# All.net
KiCad netlist of a schematic drawn in EAGLE
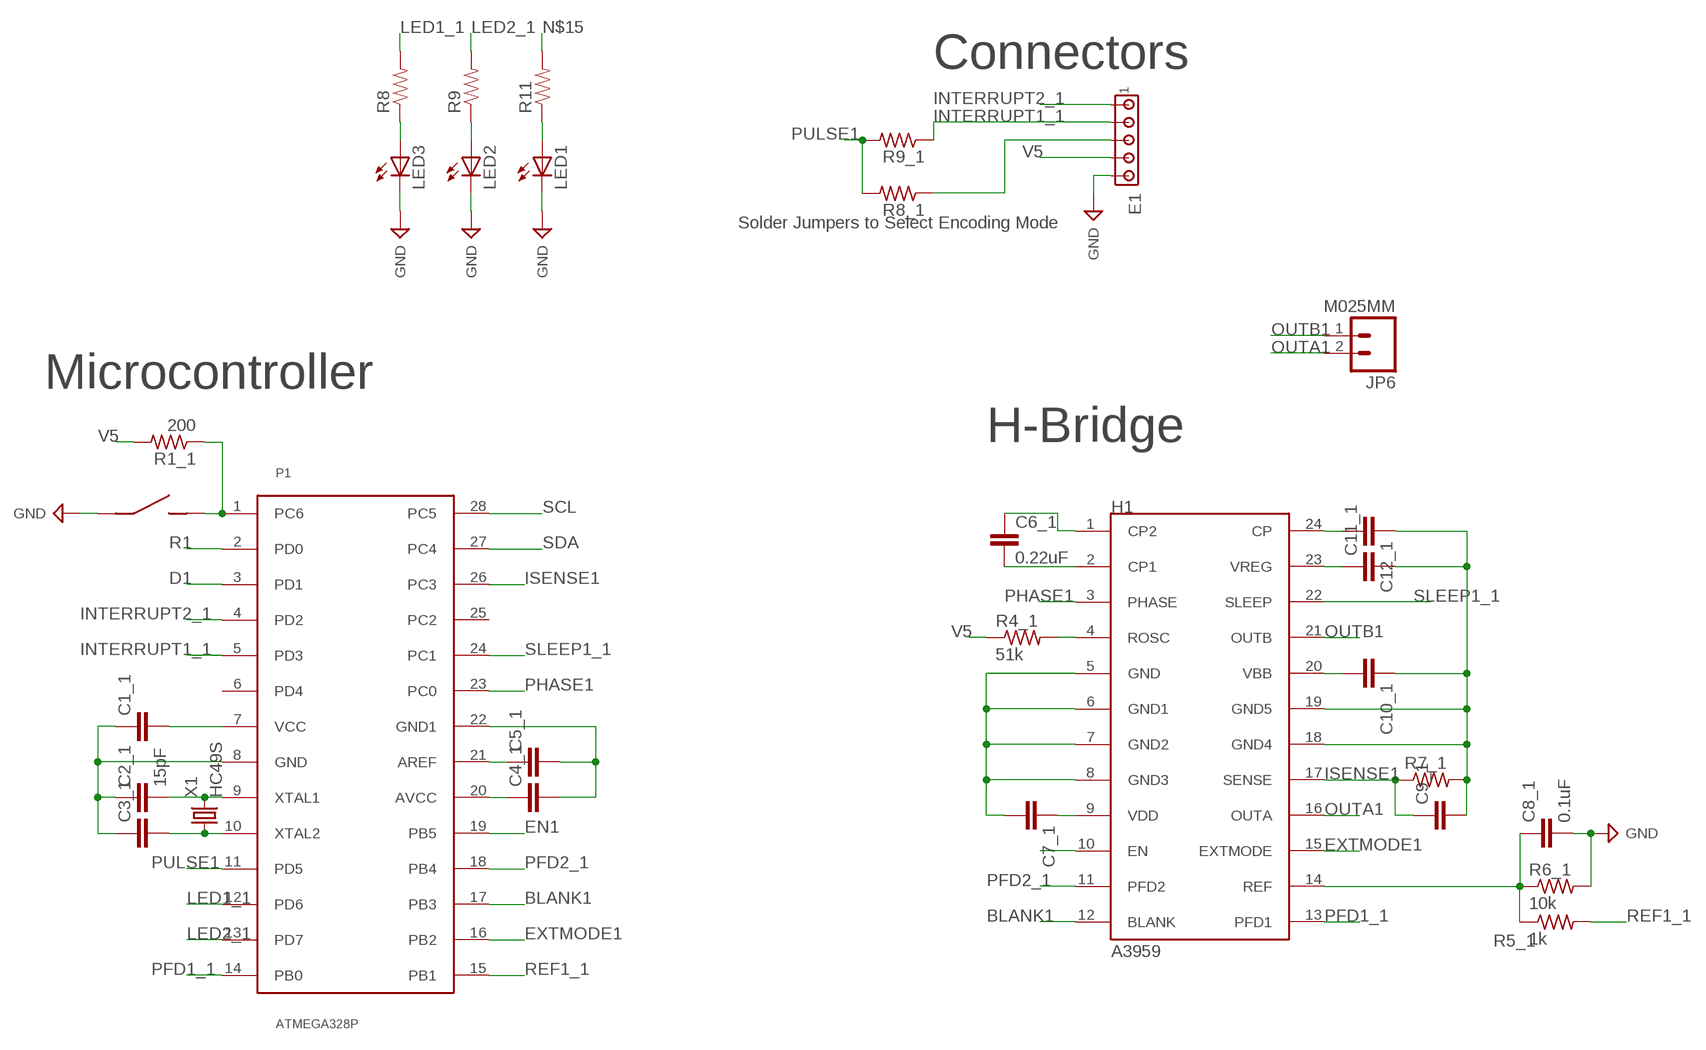
[diagram p0: schematic, sheet 1]
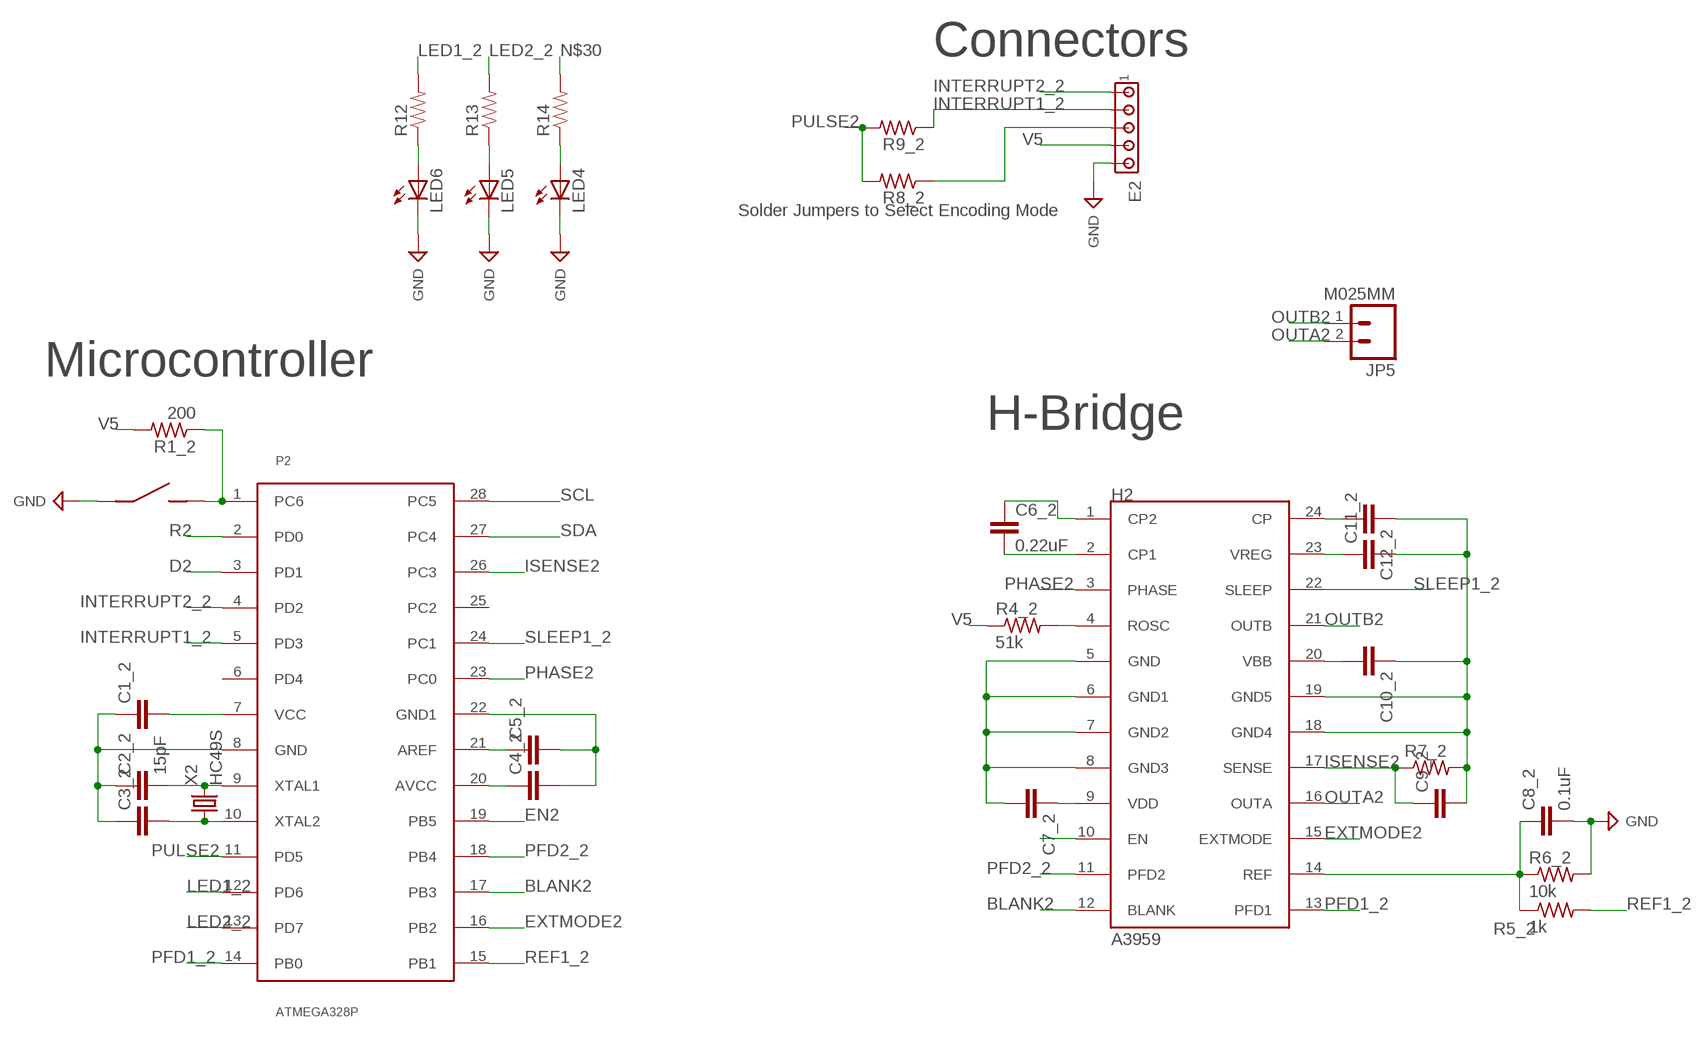
[diagram p1: schematic, sheet 2]
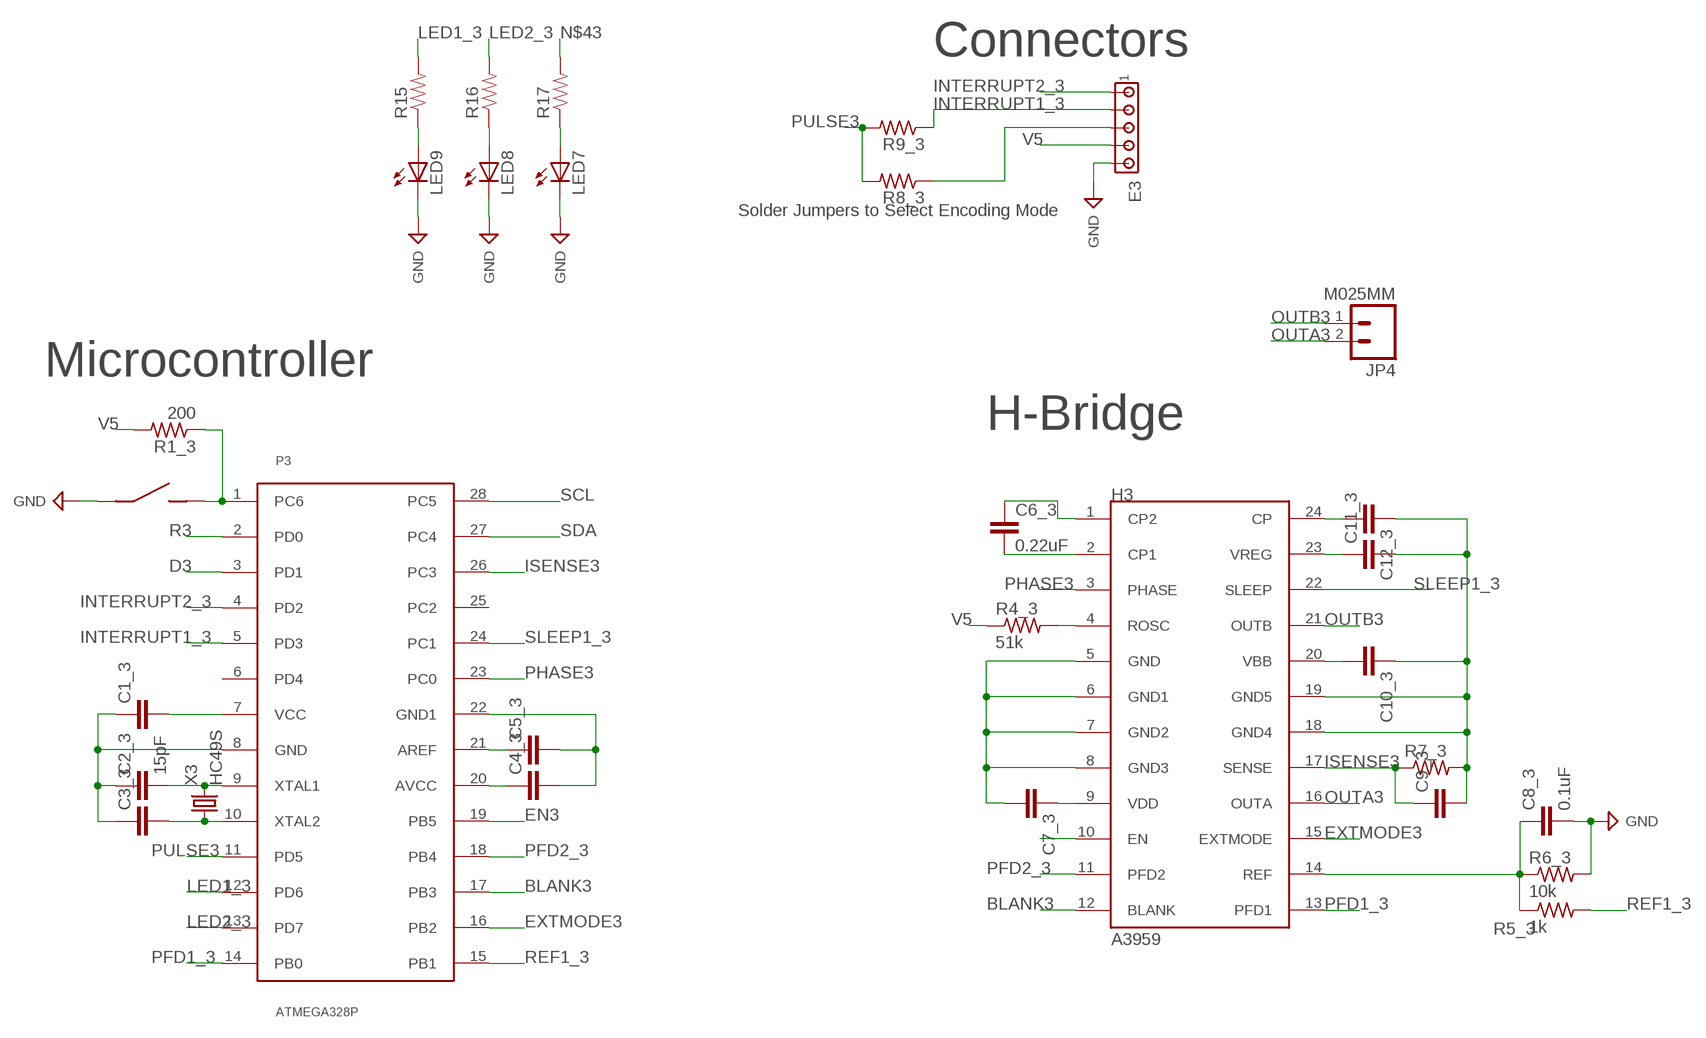
[diagram p2: schematic, sheet 3]
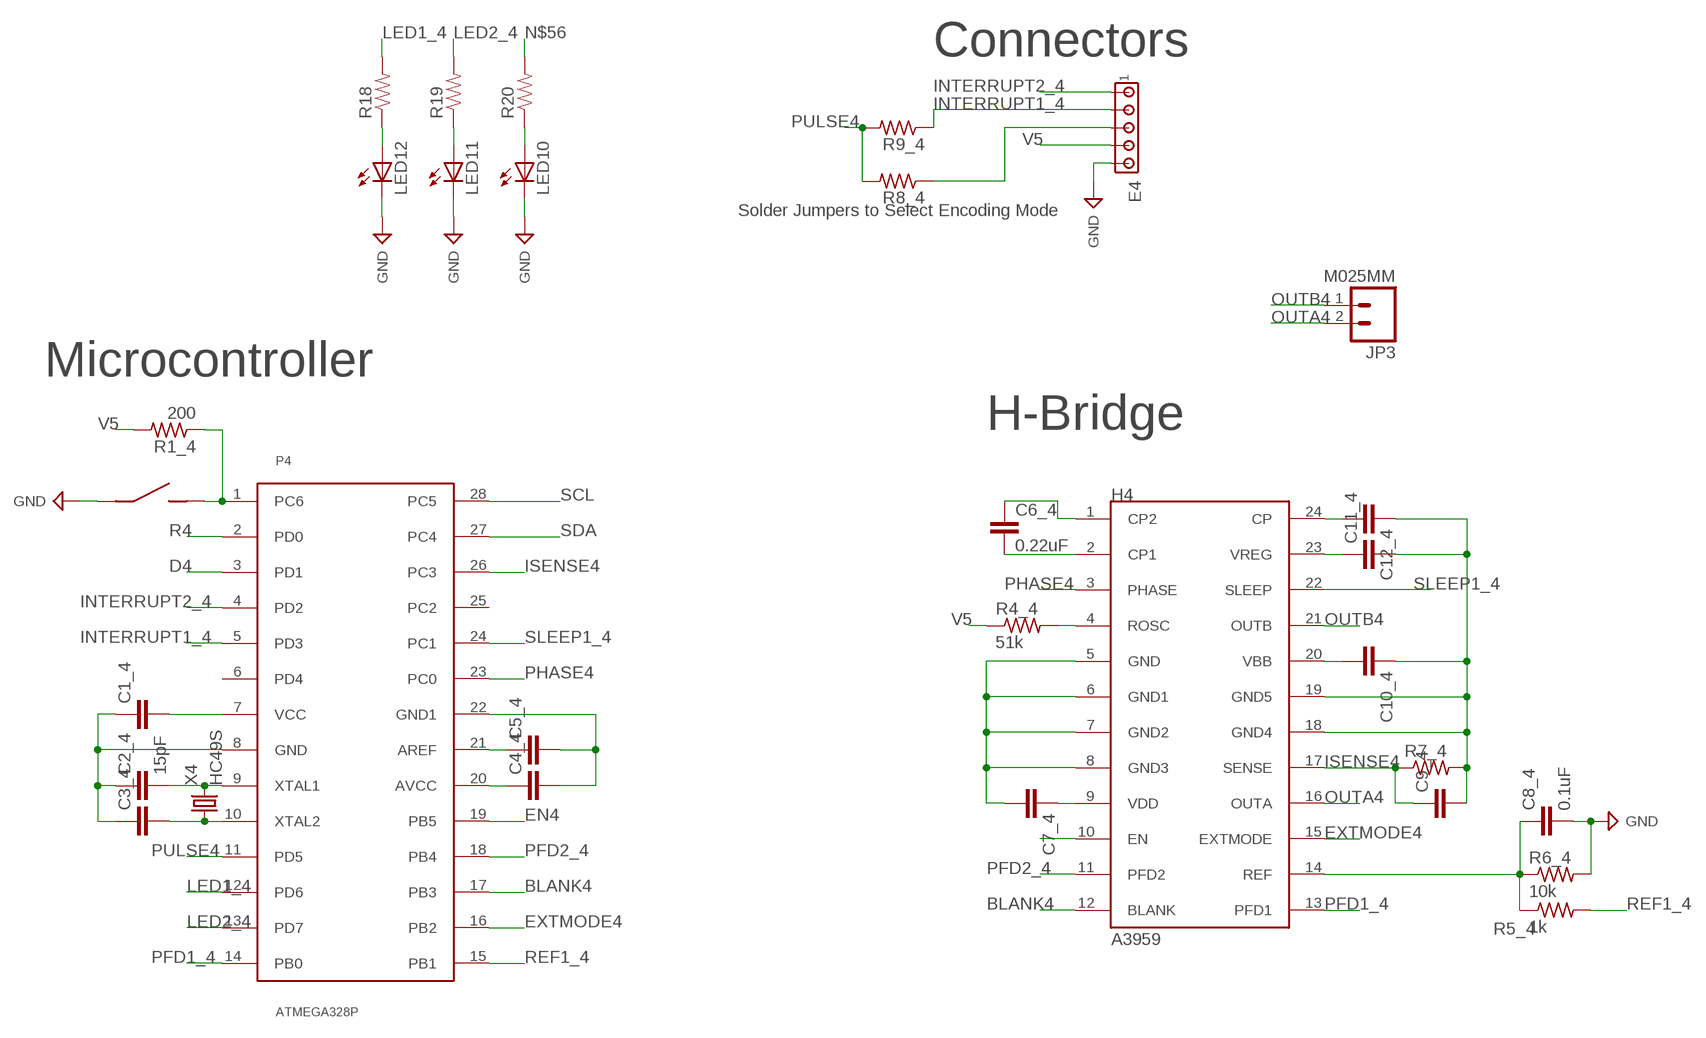
[diagram p3: schematic, sheet 4]
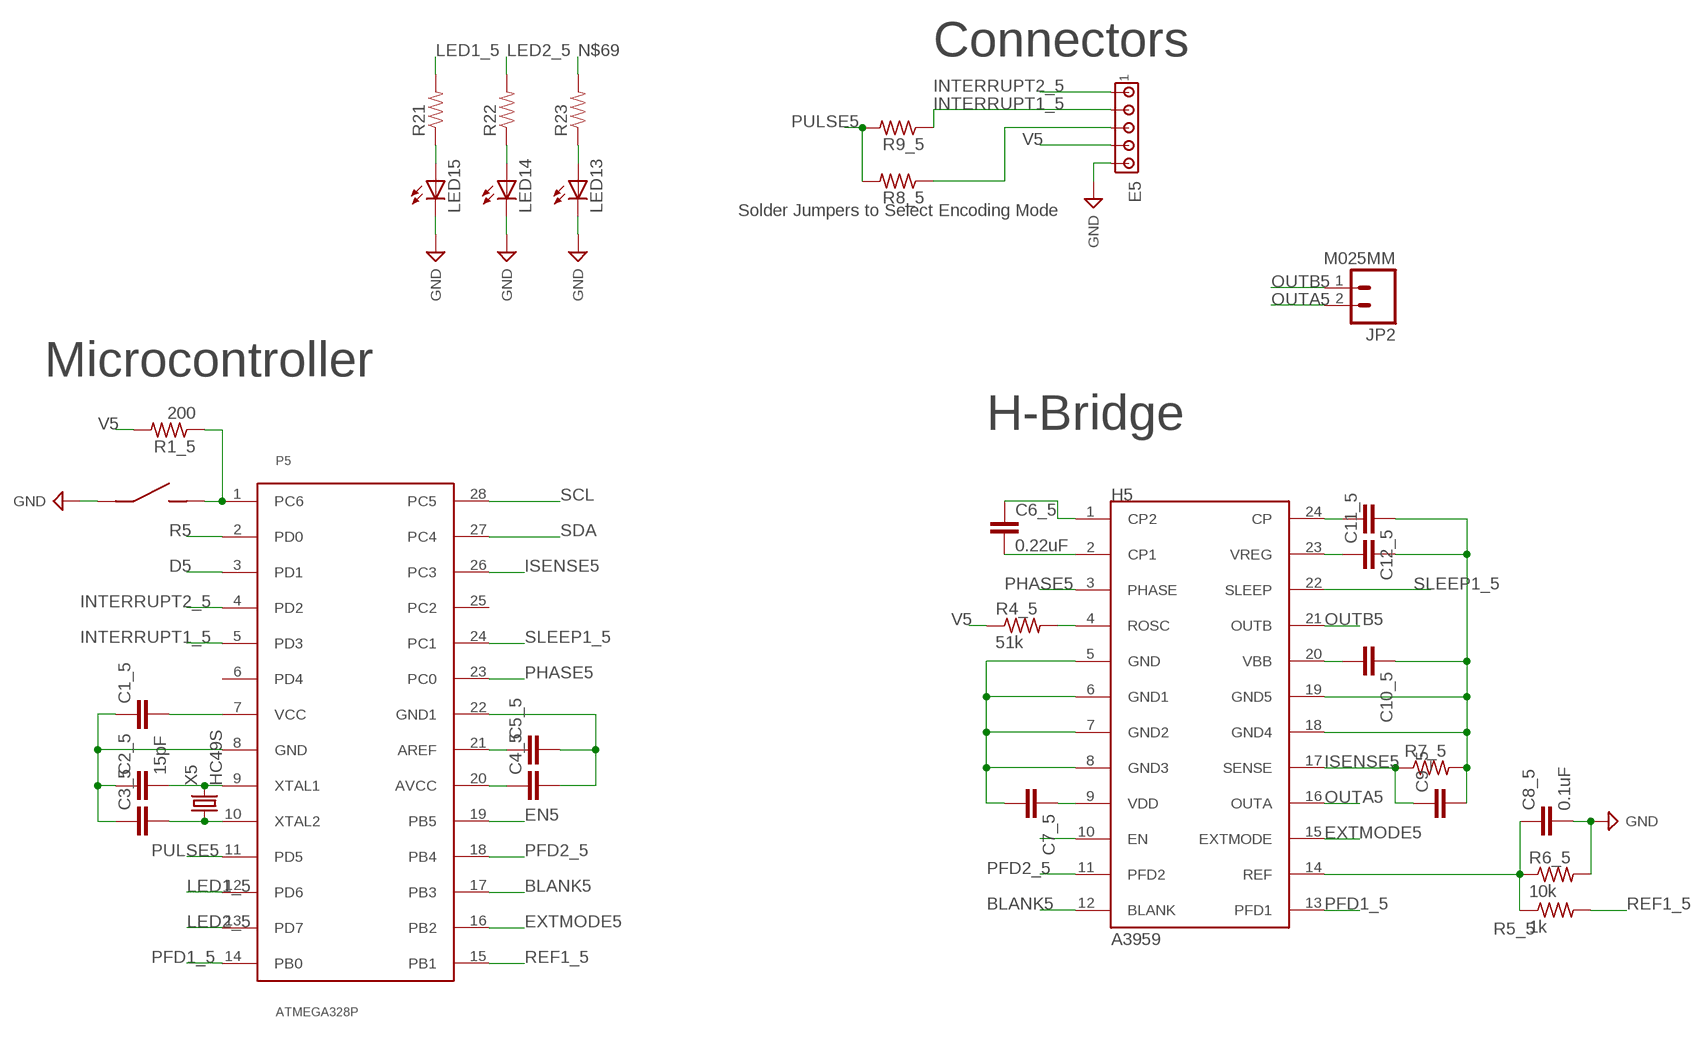
[diagram p4: schematic, sheet 5]
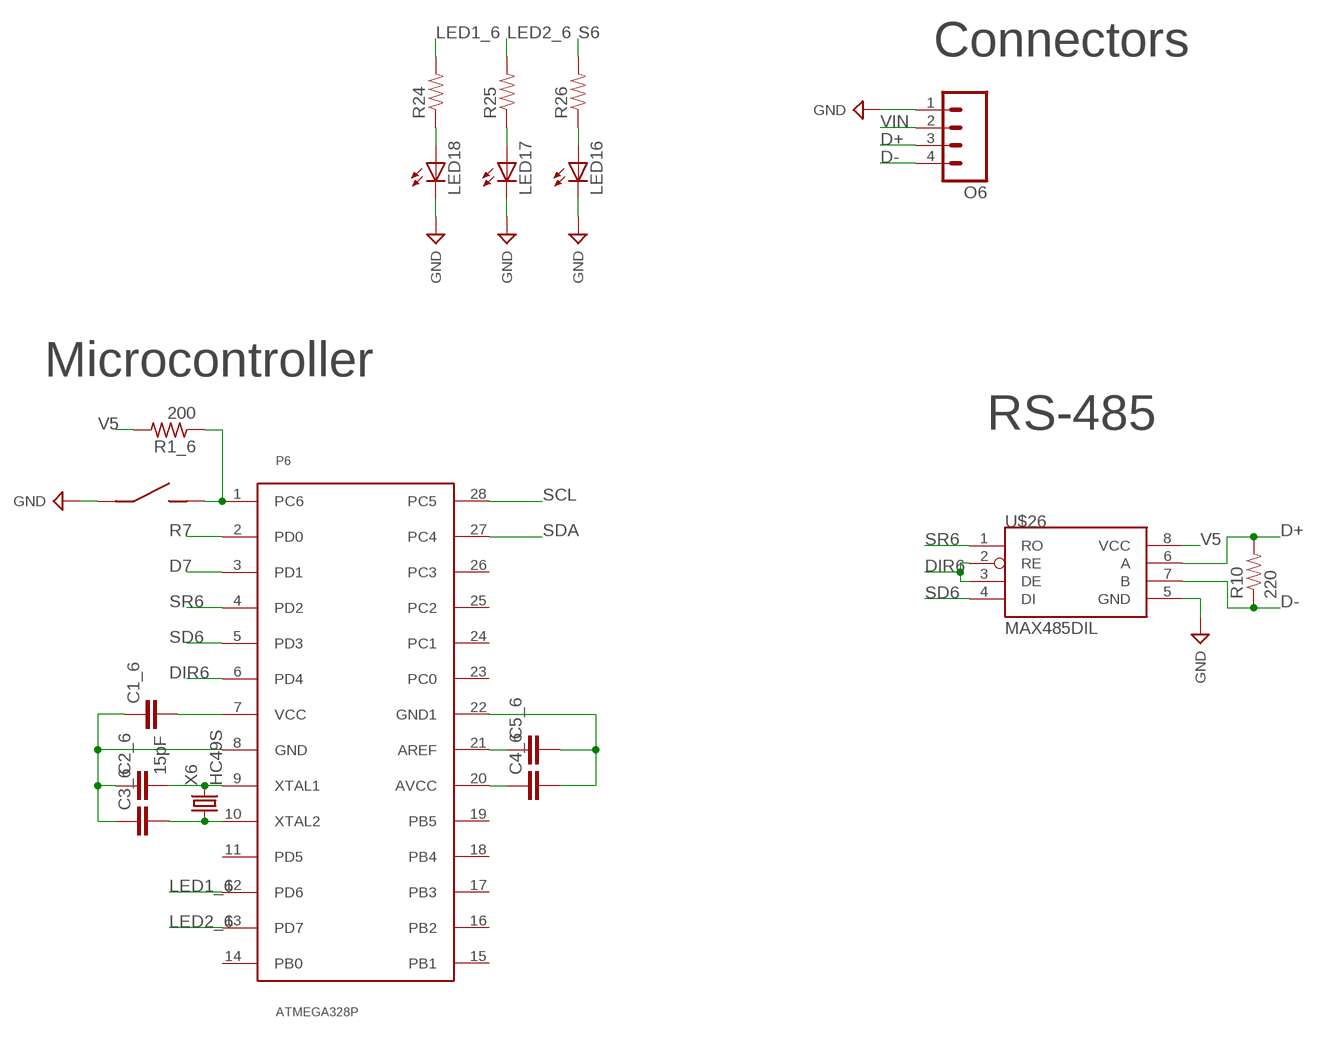
[diagram p5: schematic, sheet 6]
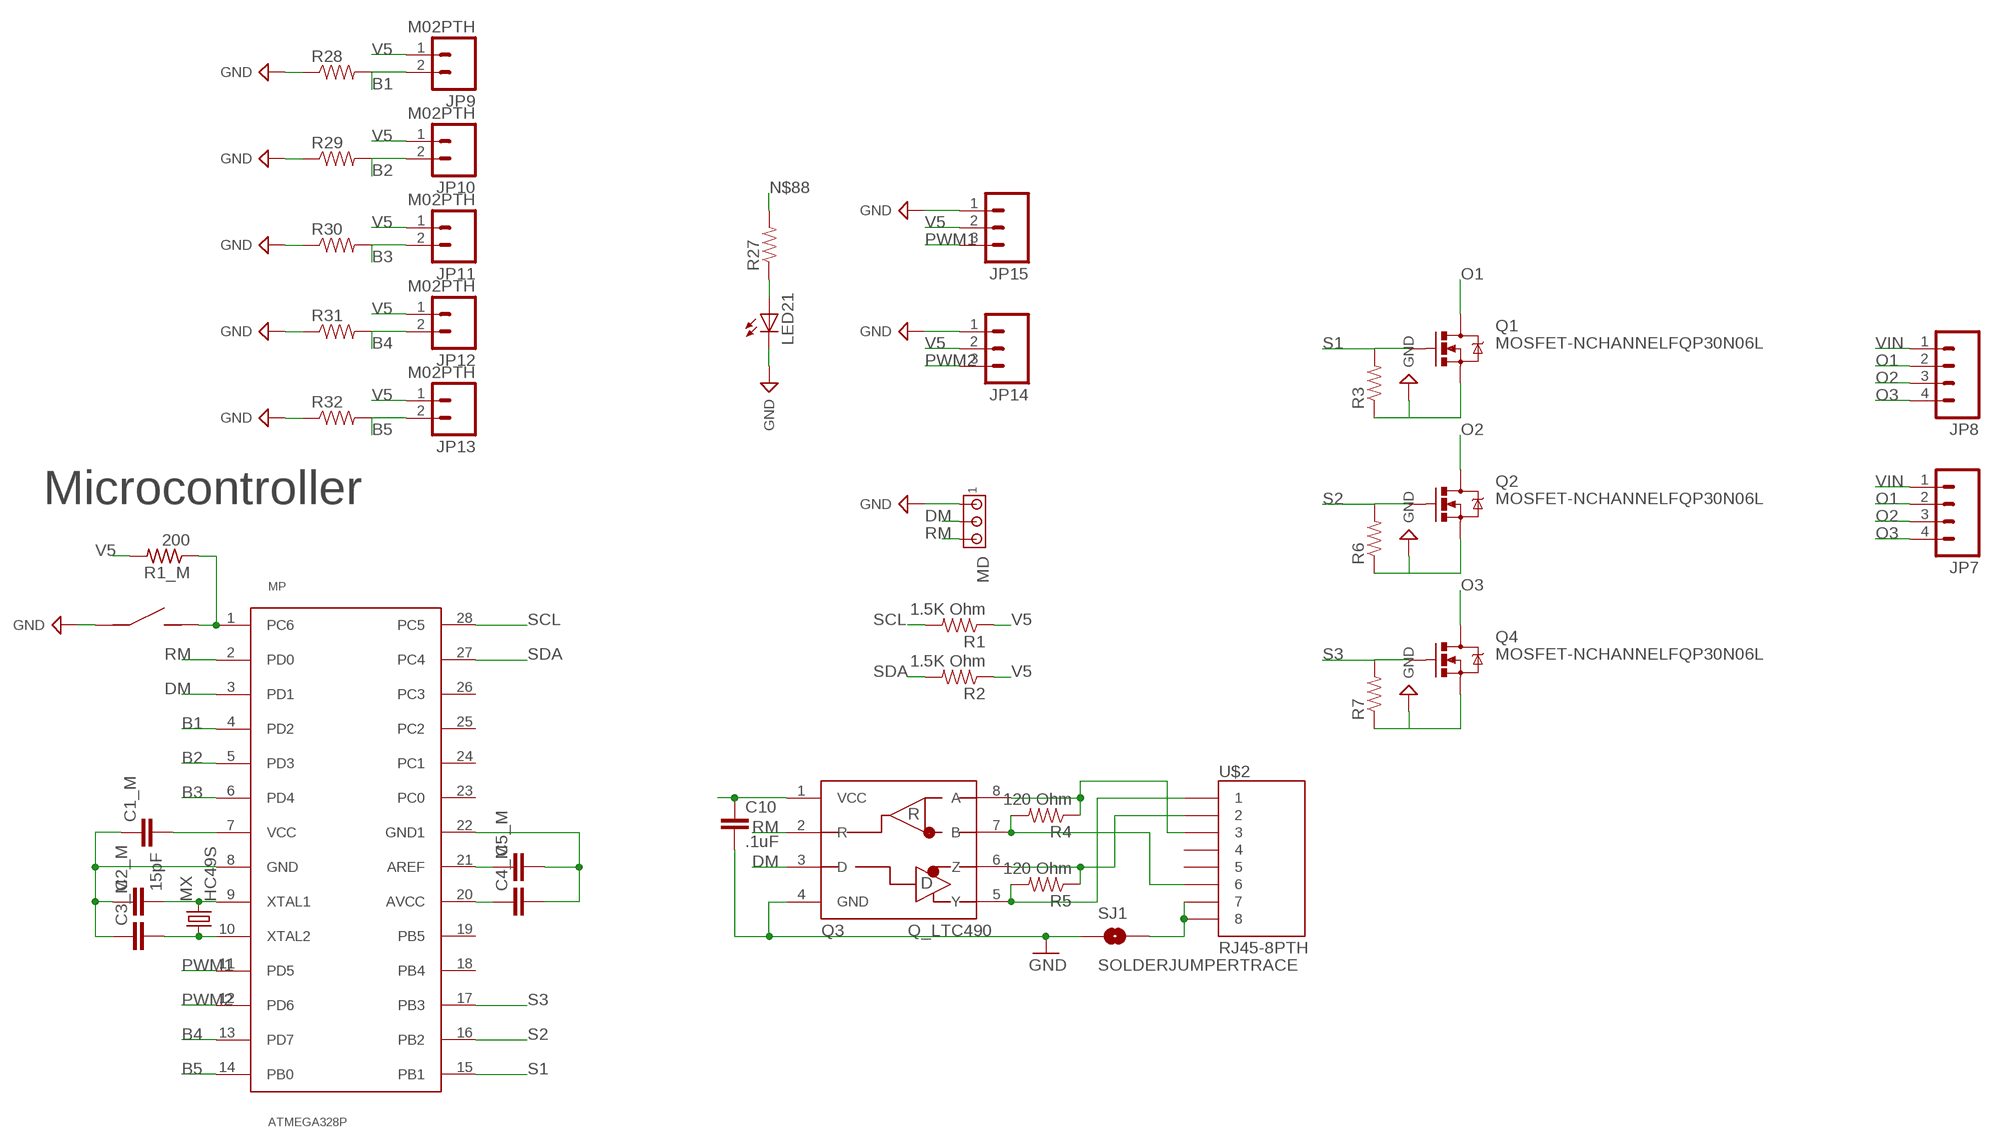
[diagram p6: schematic, sheet 7]
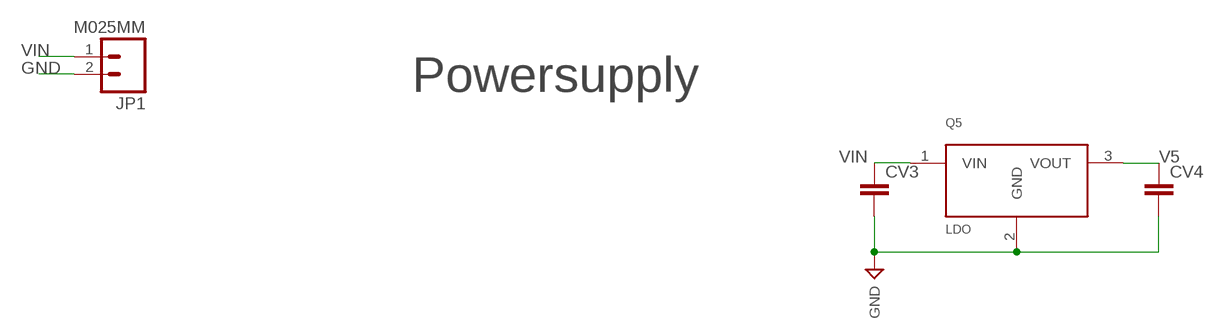
[diagram p7: schematic, sheet 8]

(export (version "E")
  (design (tool "Eeschema 10.0.6"))
  (components
    (comp (ref "CV3")
      (value "C_CAP_0805")
      (footprint "eagle-import:C_0805")
      (libsource (lib "eagle-import") (part "C_CAP_0805"))
    )
    (comp (ref "CV4")
      (value "C_CAP_0805")
      (footprint "eagle-import:C_0805")
      (libsource (lib "eagle-import") (part "C_CAP_0805"))
    )
    (comp (ref "JP1")
      (value "M025MM")
      (footprint "eagle-import:SCREWTERMINAL-5MM-2")
      (libsource (lib "eagle-import") (part "M025MM"))
    )
    (comp (ref "Q5")
      (value "LDO")
      (footprint "eagle-import:TO-220")
      (libsource (lib "eagle-import") (part "Q_LDO"))
    )
    (comp (ref "C1_2")
      (value "C_CAP_0805")
      (footprint "eagle-import:C_0805")
      (libsource (lib "eagle-import") (part "C_CAP_0805"))
    )
    (comp (ref "C2_2")
      (value "15pF")
      (footprint "eagle-import:C_0805")
      (libsource (lib "eagle-import") (part "C_CAP_0805"))
    )
    (comp (ref "C3_2")
      (value "C_CAP_0805")
      (footprint "eagle-import:C_0805")
      (libsource (lib "eagle-import") (part "C_CAP_0805"))
    )
    (comp (ref "C4_2")
      (value "C_CAP_0805")
      (footprint "eagle-import:C_0805")
      (libsource (lib "eagle-import") (part "C_CAP_0805"))
    )
    (comp (ref "C5_2")
      (value "C_CAP_0805")
      (footprint "eagle-import:C_0805")
      (libsource (lib "eagle-import") (part "C_CAP_0805"))
    )
    (comp (ref "C6_2")
      (value "0.22uF")
      (footprint "eagle-import:C_0805")
      (libsource (lib "eagle-import") (part "C_CAP_0805"))
    )
    (comp (ref "C7_2")
      (value "C_CAP_0805")
      (footprint "eagle-import:C_0805")
      (libsource (lib "eagle-import") (part "C_CAP_0805"))
    )
    (comp (ref "C8_2")
      (value "0.1uF")
      (footprint "eagle-import:C_0805")
      (libsource (lib "eagle-import") (part "C_CAP_0805"))
    )
    (comp (ref "C9_2")
      (value "C_CAP_0805")
      (footprint "eagle-import:C_0805")
      (libsource (lib "eagle-import") (part "C_CAP_0805"))
    )
    (comp (ref "C10_2")
      (value "C_CAP_0805")
      (footprint "eagle-import:C_0805")
      (libsource (lib "eagle-import") (part "C_CAP_0805"))
    )
    (comp (ref "C11_2")
      (value "C_CAP_0805")
      (footprint "eagle-import:C_0805")
      (libsource (lib "eagle-import") (part "C_CAP_0805"))
    )
    (comp (ref "C12_2")
      (value "C_CAP_0805")
      (footprint "eagle-import:C_0805")
      (libsource (lib "eagle-import") (part "C_CAP_0805"))
    )
    (comp (ref "E2")
      (value "J_MTA5P_100")
      (footprint "eagle-import:J_MTA100_5P")
      (libsource (lib "eagle-import") (part "J_MTA5P_100"))
    )
    (comp (ref "H2")
      (value "A3959")
      (footprint "eagle-import:DIP24")
      (libsource (lib "eagle-import") (part "Q_A3959"))
    )
    (comp (ref "JP5")
      (value "M025MM")
      (footprint "eagle-import:SCREWTERMINAL-5MM-2")
      (libsource (lib "eagle-import") (part "M025MM"))
    )
    (comp (ref "LED4")
      (value "LED1206")
      (footprint "eagle-import:LED-1206")
      (libsource (lib "eagle-import") (part "LED1206"))
    )
    (comp (ref "LED5")
      (value "LED1206")
      (footprint "eagle-import:LED-1206")
      (libsource (lib "eagle-import") (part "LED1206"))
    )
    (comp (ref "LED6")
      (value "LED1206")
      (footprint "eagle-import:LED-1206")
      (libsource (lib "eagle-import") (part "LED1206"))
    )
    (comp (ref "P2")
      (value "ATMEGA328P")
      (footprint "eagle-import:DIP28")
      (libsource (lib "eagle-import") (part "Q_ATMEGA328P"))
    )
    (comp (ref "R1_2")
      (value "200")
      (footprint "eagle-import:R_0805")
      (libsource (lib "eagle-import") (part "R_RES_0805"))
    )
    (comp (ref "R4_2")
      (value "51k")
      (footprint "eagle-import:R_0805")
      (libsource (lib "eagle-import") (part "R_RES_0805"))
    )
    (comp (ref "R5_2")
      (value "1k")
      (footprint "eagle-import:R_0805")
      (libsource (lib "eagle-import") (part "R_RES_0805"))
    )
    (comp (ref "R6_2")
      (value "10k")
      (footprint "eagle-import:R_0805")
      (libsource (lib "eagle-import") (part "R_RES_0805"))
    )
    (comp (ref "R7_2")
      (value "R_RES_2010")
      (footprint "eagle-import:R_2010")
      (libsource (lib "eagle-import") (part "R_RES_2010"))
    )
    (comp (ref "R8_2")
      (value "R_RES_0603")
      (footprint "eagle-import:R_0603")
      (libsource (lib "eagle-import") (part "R_RES_0603"))
    )
    (comp (ref "R9_2")
      (value "R_RES_0603")
      (footprint "eagle-import:R_0603")
      (libsource (lib "eagle-import") (part "R_RES_0603"))
    )
    (comp (ref "R12")
      (value "RESISTOR1206")
      (footprint "eagle-import:1206")
      (libsource (lib "eagle-import") (part "RESISTOR1206"))
    )
    (comp (ref "R13")
      (value "RESISTOR1206")
      (footprint "eagle-import:1206")
      (libsource (lib "eagle-import") (part "RESISTOR1206"))
    )
    (comp (ref "R14")
      (value "RESISTOR1206")
      (footprint "eagle-import:1206")
      (libsource (lib "eagle-import") (part "RESISTOR1206"))
    )
    (comp (ref "S2")
      (value "J_MC32857")
      (footprint "eagle-import:J_TOGGLE")
      (libsource (lib "eagle-import") (part "J_MC32857"))
    )
    (comp (ref "X2")
      (value "HC49S")
      (footprint "eagle-import:HC-49")
      (libsource (lib "eagle-import") (part "X_HC49SCRYSTAL"))
    )
    (comp (ref "C1_4")
      (value "C_CAP_0805")
      (footprint "eagle-import:C_0805")
      (libsource (lib "eagle-import") (part "C_CAP_0805"))
    )
    (comp (ref "C2_4")
      (value "15pF")
      (footprint "eagle-import:C_0805")
      (libsource (lib "eagle-import") (part "C_CAP_0805"))
    )
    (comp (ref "C3_4")
      (value "C_CAP_0805")
      (footprint "eagle-import:C_0805")
      (libsource (lib "eagle-import") (part "C_CAP_0805"))
    )
    (comp (ref "C4_4")
      (value "C_CAP_0805")
      (footprint "eagle-import:C_0805")
      (libsource (lib "eagle-import") (part "C_CAP_0805"))
    )
    (comp (ref "C5_4")
      (value "C_CAP_0805")
      (footprint "eagle-import:C_0805")
      (libsource (lib "eagle-import") (part "C_CAP_0805"))
    )
    (comp (ref "C6_4")
      (value "0.22uF")
      (footprint "eagle-import:C_0805")
      (libsource (lib "eagle-import") (part "C_CAP_0805"))
    )
    (comp (ref "C7_4")
      (value "C_CAP_0805")
      (footprint "eagle-import:C_0805")
      (libsource (lib "eagle-import") (part "C_CAP_0805"))
    )
    (comp (ref "C8_4")
      (value "0.1uF")
      (footprint "eagle-import:C_0805")
      (libsource (lib "eagle-import") (part "C_CAP_0805"))
    )
    (comp (ref "C9_4")
      (value "C_CAP_0805")
      (footprint "eagle-import:C_0805")
      (libsource (lib "eagle-import") (part "C_CAP_0805"))
    )
    (comp (ref "C10_4")
      (value "C_CAP_0805")
      (footprint "eagle-import:C_0805")
      (libsource (lib "eagle-import") (part "C_CAP_0805"))
    )
    (comp (ref "C11_4")
      (value "C_CAP_0805")
      (footprint "eagle-import:C_0805")
      (libsource (lib "eagle-import") (part "C_CAP_0805"))
    )
    (comp (ref "C12_4")
      (value "C_CAP_0805")
      (footprint "eagle-import:C_0805")
      (libsource (lib "eagle-import") (part "C_CAP_0805"))
    )
    (comp (ref "E4")
      (value "J_MTA5P_100")
      (footprint "eagle-import:J_MTA100_5P")
      (libsource (lib "eagle-import") (part "J_MTA5P_100"))
    )
    (comp (ref "H4")
      (value "A3959")
      (footprint "eagle-import:DIP24")
      (libsource (lib "eagle-import") (part "Q_A3959"))
    )
    (comp (ref "JP3")
      (value "M025MM")
      (footprint "eagle-import:SCREWTERMINAL-5MM-2")
      (libsource (lib "eagle-import") (part "M025MM"))
    )
    (comp (ref "LED10")
      (value "LED1206")
      (footprint "eagle-import:LED-1206")
      (libsource (lib "eagle-import") (part "LED1206"))
    )
    (comp (ref "LED11")
      (value "LED1206")
      (footprint "eagle-import:LED-1206")
      (libsource (lib "eagle-import") (part "LED1206"))
    )
    (comp (ref "LED12")
      (value "LED1206")
      (footprint "eagle-import:LED-1206")
      (libsource (lib "eagle-import") (part "LED1206"))
    )
    (comp (ref "P4")
      (value "ATMEGA328P")
      (footprint "eagle-import:DIP28")
      (libsource (lib "eagle-import") (part "Q_ATMEGA328P"))
    )
    (comp (ref "R1_4")
      (value "200")
      (footprint "eagle-import:R_0805")
      (libsource (lib "eagle-import") (part "R_RES_0805"))
    )
    (comp (ref "R4_4")
      (value "51k")
      (footprint "eagle-import:R_0805")
      (libsource (lib "eagle-import") (part "R_RES_0805"))
    )
    (comp (ref "R5_4")
      (value "1k")
      (footprint "eagle-import:R_0805")
      (libsource (lib "eagle-import") (part "R_RES_0805"))
    )
    (comp (ref "R6_4")
      (value "10k")
      (footprint "eagle-import:R_0805")
      (libsource (lib "eagle-import") (part "R_RES_0805"))
    )
    (comp (ref "R7_4")
      (value "R_RES_2010")
      (footprint "eagle-import:R_2010")
      (libsource (lib "eagle-import") (part "R_RES_2010"))
    )
    (comp (ref "R8_4")
      (value "R_RES_0603")
      (footprint "eagle-import:R_0603")
      (libsource (lib "eagle-import") (part "R_RES_0603"))
    )
    (comp (ref "R9_4")
      (value "R_RES_0603")
      (footprint "eagle-import:R_0603")
      (libsource (lib "eagle-import") (part "R_RES_0603"))
    )
    (comp (ref "R18")
      (value "RESISTOR1206")
      (footprint "eagle-import:1206")
      (libsource (lib "eagle-import") (part "RESISTOR1206"))
    )
    (comp (ref "R19")
      (value "RESISTOR1206")
      (footprint "eagle-import:1206")
      (libsource (lib "eagle-import") (part "RESISTOR1206"))
    )
    (comp (ref "R20")
      (value "RESISTOR1206")
      (footprint "eagle-import:1206")
      (libsource (lib "eagle-import") (part "RESISTOR1206"))
    )
    (comp (ref "S4")
      (value "J_MC32857")
      (footprint "eagle-import:J_TOGGLE")
      (libsource (lib "eagle-import") (part "J_MC32857"))
    )
    (comp (ref "X4")
      (value "HC49S")
      (footprint "eagle-import:HC-49")
      (libsource (lib "eagle-import") (part "X_HC49SCRYSTAL"))
    )
    (comp (ref "C1_6")
      (value "C_CAP_0805")
      (footprint "eagle-import:C_0805")
      (libsource (lib "eagle-import") (part "C_CAP_0805"))
    )
    (comp (ref "C2_6")
      (value "15pF")
      (footprint "eagle-import:C_0805")
      (libsource (lib "eagle-import") (part "C_CAP_0805"))
    )
    (comp (ref "C3_6")
      (value "C_CAP_0805")
      (footprint "eagle-import:C_0805")
      (libsource (lib "eagle-import") (part "C_CAP_0805"))
    )
    (comp (ref "C4_6")
      (value "C_CAP_0805")
      (footprint "eagle-import:C_0805")
      (libsource (lib "eagle-import") (part "C_CAP_0805"))
    )
    (comp (ref "C5_6")
      (value "C_CAP_0805")
      (footprint "eagle-import:C_0805")
      (libsource (lib "eagle-import") (part "C_CAP_0805"))
    )
    (comp (ref "J6")
      (value "J_MC32857")
      (footprint "eagle-import:J_TOGGLE")
      (libsource (lib "eagle-import") (part "J_MC32857"))
    )
    (comp (ref "LED16")
      (value "LED1206")
      (footprint "eagle-import:LED-1206")
      (libsource (lib "eagle-import") (part "LED1206"))
    )
    (comp (ref "LED17")
      (value "LED1206")
      (footprint "eagle-import:LED-1206")
      (libsource (lib "eagle-import") (part "LED1206"))
    )
    (comp (ref "LED18")
      (value "LED1206")
      (footprint "eagle-import:LED-1206")
      (libsource (lib "eagle-import") (part "LED1206"))
    )
    (comp (ref "O6")
      (value "M041X04_NO_SILK")
      (footprint "eagle-import:1X04_NO_SILK")
      (libsource (lib "eagle-import") (part "M041X04_NO_SILK"))
    )
    (comp (ref "P6")
      (value "ATMEGA328P")
      (footprint "eagle-import:DIP28")
      (libsource (lib "eagle-import") (part "Q_ATMEGA328P"))
    )
    (comp (ref "R1_6")
      (value "200")
      (footprint "eagle-import:R_0805")
      (libsource (lib "eagle-import") (part "R_RES_0805"))
    )
    (comp (ref "R10")
      (value "220")
      (footprint "eagle-import:AXIAL-0.3EZ")
      (libsource (lib "eagle-import") (part "RESISTOREZ"))
    )
    (comp (ref "R24")
      (value "RESISTOR1206")
      (footprint "eagle-import:1206")
      (libsource (lib "eagle-import") (part "RESISTOR1206"))
    )
    (comp (ref "R25")
      (value "RESISTOR1206")
      (footprint "eagle-import:1206")
      (libsource (lib "eagle-import") (part "RESISTOR1206"))
    )
    (comp (ref "R26")
      (value "RESISTOR1206")
      (footprint "eagle-import:1206")
      (libsource (lib "eagle-import") (part "RESISTOR1206"))
    )
    (comp (ref "U$26")
      (value "MAX485DIL")
      (footprint "eagle-import:DIL08")
      (libsource (lib "eagle-import") (part "MAX485DIL"))
    )
    (comp (ref "X6")
      (value "HC49S")
      (footprint "eagle-import:HC-49")
      (libsource (lib "eagle-import") (part "X_HC49SCRYSTAL"))
    )
    (comp (ref "C1_M")
      (value "C_CAP_0805")
      (footprint "eagle-import:C_0805")
      (libsource (lib "eagle-import") (part "C_CAP_0805"))
    )
    (comp (ref "C2_M")
      (value "15pF")
      (footprint "eagle-import:C_0805")
      (libsource (lib "eagle-import") (part "C_CAP_0805"))
    )
    (comp (ref "C3_M")
      (value "C_CAP_0805")
      (footprint "eagle-import:C_0805")
      (libsource (lib "eagle-import") (part "C_CAP_0805"))
    )
    (comp (ref "C4_M")
      (value "C_CAP_0805")
      (footprint "eagle-import:C_0805")
      (libsource (lib "eagle-import") (part "C_CAP_0805"))
    )
    (comp (ref "C5_M")
      (value "C_CAP_0805")
      (footprint "eagle-import:C_0805")
      (libsource (lib "eagle-import") (part "C_CAP_0805"))
    )
    (comp (ref "C10")
      (value ".1uF")
      (footprint "eagle-import:CAP-PTH-SMALL-KIT")
      (libsource (lib "eagle-import") (part "CAPKIT"))
    )
    (comp (ref "JP7")
      (value "M041X04_NO_SILK")
      (footprint "eagle-import:1X04_NO_SILK")
      (libsource (lib "eagle-import") (part "M041X04_NO_SILK"))
    )
    (comp (ref "JP8")
      (value "M041X04_NO_SILK")
      (footprint "eagle-import:1X04_NO_SILK")
      (libsource (lib "eagle-import") (part "M041X04_NO_SILK"))
    )
    (comp (ref "JP9")
      (value "M02PTH")
      (footprint "eagle-import:1X02")
      (libsource (lib "eagle-import") (part "M02PTH"))
    )
    (comp (ref "JP10")
      (value "M02PTH")
      (footprint "eagle-import:1X02")
      (libsource (lib "eagle-import") (part "M02PTH"))
    )
    (comp (ref "JP11")
      (value "M02PTH")
      (footprint "eagle-import:1X02")
      (libsource (lib "eagle-import") (part "M02PTH"))
    )
    (comp (ref "JP12")
      (value "M02PTH")
      (footprint "eagle-import:1X02")
      (libsource (lib "eagle-import") (part "M02PTH"))
    )
    (comp (ref "JP13")
      (value "M02PTH")
      (footprint "eagle-import:1X02")
      (libsource (lib "eagle-import") (part "M02PTH"))
    )
    (comp (ref "JP14")
      (value "M03PTH")
      (footprint "eagle-import:1X03")
      (libsource (lib "eagle-import") (part "M03PTH"))
    )
    (comp (ref "JP15")
      (value "M03PTH")
      (footprint "eagle-import:1X03")
      (libsource (lib "eagle-import") (part "M03PTH"))
    )
    (comp (ref "LED21")
      (value "LED1206")
      (footprint "eagle-import:LED-1206")
      (libsource (lib "eagle-import") (part "LED1206"))
    )
    (comp (ref "MD")
      (value "J_MTA3P_100")
      (footprint "eagle-import:J_MTA100_3P")
      (libsource (lib "eagle-import") (part "J_MTA3P_100"))
    )
    (comp (ref "MP")
      (value "ATMEGA328P")
      (footprint "eagle-import:DIP28")
      (libsource (lib "eagle-import") (part "Q_ATMEGA328P"))
    )
    (comp (ref "MS")
      (value "J_MC32857")
      (footprint "eagle-import:J_TOGGLE")
      (libsource (lib "eagle-import") (part "J_MC32857"))
    )
    (comp (ref "MX")
      (value "HC49S")
      (footprint "eagle-import:HC-49")
      (libsource (lib "eagle-import") (part "X_HC49SCRYSTAL"))
    )
    (comp (ref "Q1")
      (value "MOSFET-NCHANNELFQP30N06L")
      (footprint "eagle-import:TO220V")
      (libsource (lib "eagle-import") (part "MOSFET-NCHANNELFQP30N06L"))
    )
    (comp (ref "Q2")
      (value "MOSFET-NCHANNELFQP30N06L")
      (footprint "eagle-import:TO220V")
      (libsource (lib "eagle-import") (part "MOSFET-NCHANNELFQP30N06L"))
    )
    (comp (ref "Q3")
      (value "Q_LTC490")
      (footprint "eagle-import:DIP8")
      (libsource (lib "eagle-import") (part "Q_LTC490"))
    )
    (comp (ref "Q4")
      (value "MOSFET-NCHANNELFQP30N06L")
      (footprint "eagle-import:TO220V")
      (libsource (lib "eagle-import") (part "MOSFET-NCHANNELFQP30N06L"))
    )
    (comp (ref "R1")
      (value "1.5K Ohm")
      (footprint "eagle-import:AXIAL-0.3")
      (libsource (lib "eagle-import") (part "RESISTORAXIAL-0.3"))
    )
    (comp (ref "R1_M")
      (value "200")
      (footprint "eagle-import:R_0805")
      (libsource (lib "eagle-import") (part "R_RES_0805"))
    )
    (comp (ref "R2")
      (value "1.5K Ohm")
      (footprint "eagle-import:AXIAL-0.3")
      (libsource (lib "eagle-import") (part "RESISTORAXIAL-0.3"))
    )
    (comp (ref "R3")
      (value "10KOHM1/6W5%(PTH)KIT")
      (footprint "eagle-import:AXIAL-0.3-KIT")
      (libsource (lib "eagle-import") (part "10KOHM1/6W5%(PTH)KIT"))
    )
    (comp (ref "R4")
      (value "120 Ohm")
      (footprint "eagle-import:AXIAL-0.3")
      (libsource (lib "eagle-import") (part "RESISTORAXIAL-0.3"))
    )
    (comp (ref "R5")
      (value "120 Ohm")
      (footprint "eagle-import:AXIAL-0.3")
      (libsource (lib "eagle-import") (part "RESISTORAXIAL-0.3"))
    )
    (comp (ref "R6")
      (value "10KOHM1/6W5%(PTH)KIT")
      (footprint "eagle-import:AXIAL-0.3-KIT")
      (libsource (lib "eagle-import") (part "10KOHM1/6W5%(PTH)KIT"))
    )
    (comp (ref "R7")
      (value "10KOHM1/6W5%(PTH)KIT")
      (footprint "eagle-import:AXIAL-0.3-KIT")
      (libsource (lib "eagle-import") (part "10KOHM1/6W5%(PTH)KIT"))
    )
    (comp (ref "R27")
      (value "RESISTOR1206")
      (footprint "eagle-import:1206")
      (libsource (lib "eagle-import") (part "RESISTOR1206"))
    )
    (comp (ref "R28")
      (value "RESISTORPTH-1/6W")
      (footprint "eagle-import:1_6W-RES")
      (libsource (lib "eagle-import") (part "RESISTORPTH-1/6W"))
    )
    (comp (ref "R29")
      (value "RESISTORPTH-1/6W")
      (footprint "eagle-import:1_6W-RES")
      (libsource (lib "eagle-import") (part "RESISTORPTH-1/6W"))
    )
    (comp (ref "R30")
      (value "RESISTORPTH-1/6W")
      (footprint "eagle-import:1_6W-RES")
      (libsource (lib "eagle-import") (part "RESISTORPTH-1/6W"))
    )
    (comp (ref "R31")
      (value "RESISTORPTH-1/6W")
      (footprint "eagle-import:1_6W-RES")
      (libsource (lib "eagle-import") (part "RESISTORPTH-1/6W"))
    )
    (comp (ref "R32")
      (value "RESISTORPTH-1/6W")
      (footprint "eagle-import:1_6W-RES")
      (libsource (lib "eagle-import") (part "RESISTORPTH-1/6W"))
    )
    (comp (ref "SJ1")
      (value "SOLDERJUMPERTRACE")
      (footprint "eagle-import:SJ_2S-TRACE")
      (libsource (lib "eagle-import") (part "SOLDERJUMPERTRACE"))
    )
    (comp (ref "U$2")
      (value "RJ45-8PTH")
      (footprint "eagle-import:RJ45-8")
      (libsource (lib "eagle-import") (part "RJ45-8PTH"))
    )
    (comp (ref "C1_1")
      (value "C_CAP_0805")
      (footprint "eagle-import:C_0805")
      (libsource (lib "eagle-import") (part "C_CAP_0805"))
    )
    (comp (ref "C2_1")
      (value "15pF")
      (footprint "eagle-import:C_0805")
      (libsource (lib "eagle-import") (part "C_CAP_0805"))
    )
    (comp (ref "C3_1")
      (value "C_CAP_0805")
      (footprint "eagle-import:C_0805")
      (libsource (lib "eagle-import") (part "C_CAP_0805"))
    )
    (comp (ref "C4_1")
      (value "C_CAP_0805")
      (footprint "eagle-import:C_0805")
      (libsource (lib "eagle-import") (part "C_CAP_0805"))
    )
    (comp (ref "C5_1")
      (value "C_CAP_0805")
      (footprint "eagle-import:C_0805")
      (libsource (lib "eagle-import") (part "C_CAP_0805"))
    )
    (comp (ref "C6_1")
      (value "0.22uF")
      (footprint "eagle-import:C_0805")
      (libsource (lib "eagle-import") (part "C_CAP_0805"))
    )
    (comp (ref "C7_1")
      (value "C_CAP_0805")
      (footprint "eagle-import:C_0805")
      (libsource (lib "eagle-import") (part "C_CAP_0805"))
    )
    (comp (ref "C8_1")
      (value "0.1uF")
      (footprint "eagle-import:C_0805")
      (libsource (lib "eagle-import") (part "C_CAP_0805"))
    )
    (comp (ref "C9_1")
      (value "C_CAP_0805")
      (footprint "eagle-import:C_0805")
      (libsource (lib "eagle-import") (part "C_CAP_0805"))
    )
    (comp (ref "C10_1")
      (value "C_CAP_0805")
      (footprint "eagle-import:C_0805")
      (libsource (lib "eagle-import") (part "C_CAP_0805"))
    )
    (comp (ref "C11_1")
      (value "C_CAP_0805")
      (footprint "eagle-import:C_0805")
      (libsource (lib "eagle-import") (part "C_CAP_0805"))
    )
    (comp (ref "C12_1")
      (value "C_CAP_0805")
      (footprint "eagle-import:C_0805")
      (libsource (lib "eagle-import") (part "C_CAP_0805"))
    )
    (comp (ref "E1")
      (value "J_MTA5P_100")
      (footprint "eagle-import:J_MTA100_5P")
      (libsource (lib "eagle-import") (part "J_MTA5P_100"))
    )
    (comp (ref "H1")
      (value "A3959")
      (footprint "eagle-import:DIP24")
      (libsource (lib "eagle-import") (part "Q_A3959"))
    )
    (comp (ref "JP6")
      (value "M025MM")
      (footprint "eagle-import:SCREWTERMINAL-5MM-2")
      (libsource (lib "eagle-import") (part "M025MM"))
    )
    (comp (ref "LED1")
      (value "LED1206")
      (footprint "eagle-import:LED-1206")
      (libsource (lib "eagle-import") (part "LED1206"))
    )
    (comp (ref "LED2")
      (value "LED1206")
      (footprint "eagle-import:LED-1206")
      (libsource (lib "eagle-import") (part "LED1206"))
    )
    (comp (ref "LED3")
      (value "LED1206")
      (footprint "eagle-import:LED-1206")
      (libsource (lib "eagle-import") (part "LED1206"))
    )
    (comp (ref "P1")
      (value "ATMEGA328P")
      (footprint "eagle-import:DIP28")
      (libsource (lib "eagle-import") (part "Q_ATMEGA328P"))
    )
    (comp (ref "R1_1")
      (value "200")
      (footprint "eagle-import:R_0805")
      (libsource (lib "eagle-import") (part "R_RES_0805"))
    )
    (comp (ref "R4_1")
      (value "51k")
      (footprint "eagle-import:R_0805")
      (libsource (lib "eagle-import") (part "R_RES_0805"))
    )
    (comp (ref "R5_1")
      (value "1k")
      (footprint "eagle-import:R_0805")
      (libsource (lib "eagle-import") (part "R_RES_0805"))
    )
    (comp (ref "R6_1")
      (value "10k")
      (footprint "eagle-import:R_0805")
      (libsource (lib "eagle-import") (part "R_RES_0805"))
    )
    (comp (ref "R7_1")
      (value "R_RES_2010")
      (footprint "eagle-import:R_2010")
      (libsource (lib "eagle-import") (part "R_RES_2010"))
    )
    (comp (ref "R8")
      (value "RESISTOR1206")
      (footprint "eagle-import:1206")
      (libsource (lib "eagle-import") (part "RESISTOR1206"))
    )
    (comp (ref "R8_1")
      (value "R_RES_0603")
      (footprint "eagle-import:R_0603")
      (libsource (lib "eagle-import") (part "R_RES_0603"))
    )
    (comp (ref "R9")
      (value "RESISTOR1206")
      (footprint "eagle-import:1206")
      (libsource (lib "eagle-import") (part "RESISTOR1206"))
    )
    (comp (ref "R9_1")
      (value "R_RES_0603")
      (footprint "eagle-import:R_0603")
      (libsource (lib "eagle-import") (part "R_RES_0603"))
    )
    (comp (ref "R11")
      (value "RESISTOR1206")
      (footprint "eagle-import:1206")
      (libsource (lib "eagle-import") (part "RESISTOR1206"))
    )
    (comp (ref "S1")
      (value "J_MC32857")
      (footprint "eagle-import:J_TOGGLE")
      (libsource (lib "eagle-import") (part "J_MC32857"))
    )
    (comp (ref "X1")
      (value "HC49S")
      (footprint "eagle-import:HC-49")
      (libsource (lib "eagle-import") (part "X_HC49SCRYSTAL"))
    )
    (comp (ref "C1_3")
      (value "C_CAP_0805")
      (footprint "eagle-import:C_0805")
      (libsource (lib "eagle-import") (part "C_CAP_0805"))
    )
    (comp (ref "C2_3")
      (value "15pF")
      (footprint "eagle-import:C_0805")
      (libsource (lib "eagle-import") (part "C_CAP_0805"))
    )
    (comp (ref "C3_3")
      (value "C_CAP_0805")
      (footprint "eagle-import:C_0805")
      (libsource (lib "eagle-import") (part "C_CAP_0805"))
    )
    (comp (ref "C4_3")
      (value "C_CAP_0805")
      (footprint "eagle-import:C_0805")
      (libsource (lib "eagle-import") (part "C_CAP_0805"))
    )
    (comp (ref "C5_3")
      (value "C_CAP_0805")
      (footprint "eagle-import:C_0805")
      (libsource (lib "eagle-import") (part "C_CAP_0805"))
    )
    (comp (ref "C6_3")
      (value "0.22uF")
      (footprint "eagle-import:C_0805")
      (libsource (lib "eagle-import") (part "C_CAP_0805"))
    )
    (comp (ref "C7_3")
      (value "C_CAP_0805")
      (footprint "eagle-import:C_0805")
      (libsource (lib "eagle-import") (part "C_CAP_0805"))
    )
    (comp (ref "C8_3")
      (value "0.1uF")
      (footprint "eagle-import:C_0805")
      (libsource (lib "eagle-import") (part "C_CAP_0805"))
    )
    (comp (ref "C9_3")
      (value "C_CAP_0805")
      (footprint "eagle-import:C_0805")
      (libsource (lib "eagle-import") (part "C_CAP_0805"))
    )
    (comp (ref "C10_3")
      (value "C_CAP_0805")
      (footprint "eagle-import:C_0805")
      (libsource (lib "eagle-import") (part "C_CAP_0805"))
    )
    (comp (ref "C11_3")
      (value "C_CAP_0805")
      (footprint "eagle-import:C_0805")
      (libsource (lib "eagle-import") (part "C_CAP_0805"))
    )
    (comp (ref "C12_3")
      (value "C_CAP_0805")
      (footprint "eagle-import:C_0805")
      (libsource (lib "eagle-import") (part "C_CAP_0805"))
    )
    (comp (ref "E3")
      (value "J_MTA5P_100")
      (footprint "eagle-import:J_MTA100_5P")
      (libsource (lib "eagle-import") (part "J_MTA5P_100"))
    )
    (comp (ref "H3")
      (value "A3959")
      (footprint "eagle-import:DIP24")
      (libsource (lib "eagle-import") (part "Q_A3959"))
    )
    (comp (ref "JP4")
      (value "M025MM")
      (footprint "eagle-import:SCREWTERMINAL-5MM-2")
      (libsource (lib "eagle-import") (part "M025MM"))
    )
    (comp (ref "LED7")
      (value "LED1206")
      (footprint "eagle-import:LED-1206")
      (libsource (lib "eagle-import") (part "LED1206"))
    )
    (comp (ref "LED8")
      (value "LED1206")
      (footprint "eagle-import:LED-1206")
      (libsource (lib "eagle-import") (part "LED1206"))
    )
    (comp (ref "LED9")
      (value "LED1206")
      (footprint "eagle-import:LED-1206")
      (libsource (lib "eagle-import") (part "LED1206"))
    )
    (comp (ref "P3")
      (value "ATMEGA328P")
      (footprint "eagle-import:DIP28")
      (libsource (lib "eagle-import") (part "Q_ATMEGA328P"))
    )
    (comp (ref "R1_3")
      (value "200")
      (footprint "eagle-import:R_0805")
      (libsource (lib "eagle-import") (part "R_RES_0805"))
    )
    (comp (ref "R4_3")
      (value "51k")
      (footprint "eagle-import:R_0805")
      (libsource (lib "eagle-import") (part "R_RES_0805"))
    )
    (comp (ref "R5_3")
      (value "1k")
      (footprint "eagle-import:R_0805")
      (libsource (lib "eagle-import") (part "R_RES_0805"))
    )
    (comp (ref "R6_3")
      (value "10k")
      (footprint "eagle-import:R_0805")
      (libsource (lib "eagle-import") (part "R_RES_0805"))
    )
    (comp (ref "R7_3")
      (value "R_RES_2010")
      (footprint "eagle-import:R_2010")
      (libsource (lib "eagle-import") (part "R_RES_2010"))
    )
    (comp (ref "R8_3")
      (value "R_RES_0603")
      (footprint "eagle-import:R_0603")
      (libsource (lib "eagle-import") (part "R_RES_0603"))
    )
    (comp (ref "R9_3")
      (value "R_RES_0603")
      (footprint "eagle-import:R_0603")
      (libsource (lib "eagle-import") (part "R_RES_0603"))
    )
    (comp (ref "R15")
      (value "RESISTOR1206")
      (footprint "eagle-import:1206")
      (libsource (lib "eagle-import") (part "RESISTOR1206"))
    )
    (comp (ref "R16")
      (value "RESISTOR1206")
      (footprint "eagle-import:1206")
      (libsource (lib "eagle-import") (part "RESISTOR1206"))
    )
    (comp (ref "R17")
      (value "RESISTOR1206")
      (footprint "eagle-import:1206")
      (libsource (lib "eagle-import") (part "RESISTOR1206"))
    )
    (comp (ref "S3")
      (value "J_MC32857")
      (footprint "eagle-import:J_TOGGLE")
      (libsource (lib "eagle-import") (part "J_MC32857"))
    )
    (comp (ref "X3")
      (value "HC49S")
      (footprint "eagle-import:HC-49")
      (libsource (lib "eagle-import") (part "X_HC49SCRYSTAL"))
    )
    (comp (ref "C1_5")
      (value "C_CAP_0805")
      (footprint "eagle-import:C_0805")
      (libsource (lib "eagle-import") (part "C_CAP_0805"))
    )
    (comp (ref "C2_5")
      (value "15pF")
      (footprint "eagle-import:C_0805")
      (libsource (lib "eagle-import") (part "C_CAP_0805"))
    )
    (comp (ref "C3_5")
      (value "C_CAP_0805")
      (footprint "eagle-import:C_0805")
      (libsource (lib "eagle-import") (part "C_CAP_0805"))
    )
    (comp (ref "C4_5")
      (value "C_CAP_0805")
      (footprint "eagle-import:C_0805")
      (libsource (lib "eagle-import") (part "C_CAP_0805"))
    )
    (comp (ref "C5_5")
      (value "C_CAP_0805")
      (footprint "eagle-import:C_0805")
      (libsource (lib "eagle-import") (part "C_CAP_0805"))
    )
    (comp (ref "C6_5")
      (value "0.22uF")
      (footprint "eagle-import:C_0805")
      (libsource (lib "eagle-import") (part "C_CAP_0805"))
    )
    (comp (ref "C7_5")
      (value "C_CAP_0805")
      (footprint "eagle-import:C_0805")
      (libsource (lib "eagle-import") (part "C_CAP_0805"))
    )
    (comp (ref "C8_5")
      (value "0.1uF")
      (footprint "eagle-import:C_0805")
      (libsource (lib "eagle-import") (part "C_CAP_0805"))
    )
    (comp (ref "C9_5")
      (value "C_CAP_0805")
      (footprint "eagle-import:C_0805")
      (libsource (lib "eagle-import") (part "C_CAP_0805"))
    )
    (comp (ref "C10_5")
      (value "C_CAP_0805")
      (footprint "eagle-import:C_0805")
      (libsource (lib "eagle-import") (part "C_CAP_0805"))
    )
    (comp (ref "C11_5")
      (value "C_CAP_0805")
      (footprint "eagle-import:C_0805")
      (libsource (lib "eagle-import") (part "C_CAP_0805"))
    )
    (comp (ref "C12_5")
      (value "C_CAP_0805")
      (footprint "eagle-import:C_0805")
      (libsource (lib "eagle-import") (part "C_CAP_0805"))
    )
    (comp (ref "E5")
      (value "J_MTA5P_100")
      (footprint "eagle-import:J_MTA100_5P")
      (libsource (lib "eagle-import") (part "J_MTA5P_100"))
    )
    (comp (ref "H5")
      (value "A3959")
      (footprint "eagle-import:DIP24")
      (libsource (lib "eagle-import") (part "Q_A3959"))
    )
    (comp (ref "JP2")
      (value "M025MM")
      (footprint "eagle-import:SCREWTERMINAL-5MM-2")
      (libsource (lib "eagle-import") (part "M025MM"))
    )
    (comp (ref "LED13")
      (value "LED1206")
      (footprint "eagle-import:LED-1206")
      (libsource (lib "eagle-import") (part "LED1206"))
    )
    (comp (ref "LED14")
      (value "LED1206")
      (footprint "eagle-import:LED-1206")
      (libsource (lib "eagle-import") (part "LED1206"))
    )
    (comp (ref "LED15")
      (value "LED1206")
      (footprint "eagle-import:LED-1206")
      (libsource (lib "eagle-import") (part "LED1206"))
    )
    (comp (ref "P5")
      (value "ATMEGA328P")
      (footprint "eagle-import:DIP28")
      (libsource (lib "eagle-import") (part "Q_ATMEGA328P"))
    )
    (comp (ref "R1_5")
      (value "200")
      (footprint "eagle-import:R_0805")
      (libsource (lib "eagle-import") (part "R_RES_0805"))
    )
    (comp (ref "R4_5")
      (value "51k")
      (footprint "eagle-import:R_0805")
      (libsource (lib "eagle-import") (part "R_RES_0805"))
    )
    (comp (ref "R5_5")
      (value "1k")
      (footprint "eagle-import:R_0805")
      (libsource (lib "eagle-import") (part "R_RES_0805"))
    )
    (comp (ref "R6_5")
      (value "10k")
      (footprint "eagle-import:R_0805")
      (libsource (lib "eagle-import") (part "R_RES_0805"))
    )
    (comp (ref "R7_5")
      (value "R_RES_2010")
      (footprint "eagle-import:R_2010")
      (libsource (lib "eagle-import") (part "R_RES_2010"))
    )
    (comp (ref "R8_5")
      (value "R_RES_0603")
      (footprint "eagle-import:R_0603")
      (libsource (lib "eagle-import") (part "R_RES_0603"))
    )
    (comp (ref "R9_5")
      (value "R_RES_0603")
      (footprint "eagle-import:R_0603")
      (libsource (lib "eagle-import") (part "R_RES_0603"))
    )
    (comp (ref "R21")
      (value "RESISTOR1206")
      (footprint "eagle-import:1206")
      (libsource (lib "eagle-import") (part "RESISTOR1206"))
    )
    (comp (ref "R22")
      (value "RESISTOR1206")
      (footprint "eagle-import:1206")
      (libsource (lib "eagle-import") (part "RESISTOR1206"))
    )
    (comp (ref "R23")
      (value "RESISTOR1206")
      (footprint "eagle-import:1206")
      (libsource (lib "eagle-import") (part "RESISTOR1206"))
    )
    (comp (ref "S5")
      (value "J_MC32857")
      (footprint "eagle-import:J_TOGGLE")
      (libsource (lib "eagle-import") (part "J_MC32857"))
    )
    (comp (ref "X5")
      (value "HC49S")
      (footprint "eagle-import:HC-49")
      (libsource (lib "eagle-import") (part "X_HC49SCRYSTAL"))
    )
  )
  (nets
    (net (code "1") (name "B1") (class "Default")
      (node (ref "JP9") (pin "2") (pinfunction "2_2") (pintype "passive"))
      (node (ref "MP") (pin "4") (pinfunction "PD2_4") (pintype "bidirectional"))
      (node (ref "R28") (pin "2") (pinfunction "2_2") (pintype "passive"))
    )
    (net (code "2") (name "B2") (class "Default")
      (node (ref "JP10") (pin "2") (pinfunction "2_2") (pintype "passive"))
      (node (ref "MP") (pin "5") (pinfunction "PD3_5") (pintype "bidirectional"))
      (node (ref "R29") (pin "2") (pinfunction "2_2") (pintype "passive"))
    )
    (net (code "3") (name "B3") (class "Default")
      (node (ref "JP11") (pin "2") (pinfunction "2_2") (pintype "passive"))
      (node (ref "MP") (pin "6") (pinfunction "PD4_6") (pintype "bidirectional"))
      (node (ref "R30") (pin "2") (pinfunction "2_2") (pintype "passive"))
    )
    (net (code "4") (name "B4") (class "Default")
      (node (ref "JP12") (pin "2") (pinfunction "2_2") (pintype "passive"))
      (node (ref "MP") (pin "13") (pinfunction "PD7_13") (pintype "bidirectional"))
      (node (ref "R31") (pin "2") (pinfunction "2_2") (pintype "passive"))
    )
    (net (code "5") (name "B5") (class "Default")
      (node (ref "JP13") (pin "2") (pinfunction "2_2") (pintype "passive"))
      (node (ref "MP") (pin "14") (pinfunction "PB0_14") (pintype "bidirectional"))
      (node (ref "R32") (pin "2") (pinfunction "2_2") (pintype "passive"))
    )
    (net (code "6") (name "BLANK1") (class "Default")
      (node (ref "H1") (pin "12") (pinfunction "BLANK_12") (pintype "bidirectional"))
      (node (ref "P1") (pin "17") (pinfunction "PB3_17") (pintype "bidirectional"))
    )
    (net (code "7") (name "BLANK2") (class "Default")
      (node (ref "H2") (pin "12") (pinfunction "BLANK_12") (pintype "bidirectional"))
      (node (ref "P2") (pin "17") (pinfunction "PB3_17") (pintype "bidirectional"))
    )
    (net (code "8") (name "BLANK3") (class "Default")
      (node (ref "H3") (pin "12") (pinfunction "BLANK_12") (pintype "bidirectional"))
      (node (ref "P3") (pin "17") (pinfunction "PB3_17") (pintype "bidirectional"))
    )
    (net (code "9") (name "BLANK4") (class "Default")
      (node (ref "H4") (pin "12") (pinfunction "BLANK_12") (pintype "bidirectional"))
      (node (ref "P4") (pin "17") (pinfunction "PB3_17") (pintype "bidirectional"))
    )
    (net (code "10") (name "BLANK5") (class "Default")
      (node (ref "H5") (pin "12") (pinfunction "BLANK_12") (pintype "bidirectional"))
      (node (ref "P5") (pin "17") (pinfunction "PB3_17") (pintype "bidirectional"))
    )
    (net (code "11") (name "D+") (class "Default")
      (node (ref "O6") (pin "3") (pinfunction "3_3") (pintype "passive"))
      (node (ref "R10") (pin "P$2") (pinfunction "2_P$2") (pintype "passive"))
      (node (ref "U$26") (pin "6") (pinfunction "A_6") (pintype "bidirectional"))
    )
    (net (code "12") (name "D-") (class "Default")
      (node (ref "O6") (pin "4") (pinfunction "4_4") (pintype "passive"))
      (node (ref "R10") (pin "P$1") (pinfunction "1_P$1") (pintype "passive"))
      (node (ref "U$26") (pin "7") (pinfunction "B_7") (pintype "bidirectional"))
    )
    (net (code "13") (name "D1") (class "Default")
      (node (ref "P1") (pin "3") (pinfunction "PD1_3") (pintype "bidirectional"))
    )
    (net (code "14") (name "D2") (class "Default")
      (node (ref "P2") (pin "3") (pinfunction "PD1_3") (pintype "bidirectional"))
    )
    (net (code "15") (name "D3") (class "Default")
      (node (ref "P3") (pin "3") (pinfunction "PD1_3") (pintype "bidirectional"))
    )
    (net (code "16") (name "D4") (class "Default")
      (node (ref "P4") (pin "3") (pinfunction "PD1_3") (pintype "bidirectional"))
    )
    (net (code "17") (name "D5") (class "Default")
      (node (ref "P5") (pin "3") (pinfunction "PD1_3") (pintype "bidirectional"))
    )
    (net (code "18") (name "D7") (class "Default")
      (node (ref "P6") (pin "3") (pinfunction "PD1_3") (pintype "bidirectional"))
    )
    (net (code "19") (name "DIR6") (class "Default")
      (node (ref "P6") (pin "6") (pinfunction "PD4_6") (pintype "bidirectional"))
      (node (ref "U$26") (pin "2") (pinfunction "RE_2") (pintype "bidirectional"))
      (node (ref "U$26") (pin "3") (pinfunction "DE_3") (pintype "bidirectional"))
    )
    (net (code "20") (name "DM") (class "Default")
      (node (ref "MD") (pin "2") (pinfunction "2_2") (pintype "passive"))
      (node (ref "MP") (pin "3") (pinfunction "PD1_3") (pintype "bidirectional"))
      (node (ref "Q3") (pin "3") (pinfunction "D_3") (pintype "bidirectional"))
    )
    (net (code "21") (name "EN1") (class "Default")
      (node (ref "H1") (pin "10") (pinfunction "EN_10") (pintype "bidirectional"))
      (node (ref "P1") (pin "19") (pinfunction "PB5_19") (pintype "bidirectional"))
    )
    (net (code "22") (name "EN2") (class "Default")
      (node (ref "H2") (pin "10") (pinfunction "EN_10") (pintype "bidirectional"))
      (node (ref "P2") (pin "19") (pinfunction "PB5_19") (pintype "bidirectional"))
    )
    (net (code "23") (name "EN3") (class "Default")
      (node (ref "H3") (pin "10") (pinfunction "EN_10") (pintype "bidirectional"))
      (node (ref "P3") (pin "19") (pinfunction "PB5_19") (pintype "bidirectional"))
    )
    (net (code "24") (name "EN4") (class "Default")
      (node (ref "H4") (pin "10") (pinfunction "EN_10") (pintype "bidirectional"))
      (node (ref "P4") (pin "19") (pinfunction "PB5_19") (pintype "bidirectional"))
    )
    (net (code "25") (name "EN5") (class "Default")
      (node (ref "H5") (pin "10") (pinfunction "EN_10") (pintype "bidirectional"))
      (node (ref "P5") (pin "19") (pinfunction "PB5_19") (pintype "bidirectional"))
    )
    (net (code "26") (name "EXTMODE1") (class "Default")
      (node (ref "H1") (pin "15") (pinfunction "EXTMODE_15") (pintype "bidirectional"))
      (node (ref "P1") (pin "16") (pinfunction "PB2_16") (pintype "bidirectional"))
    )
    (net (code "27") (name "EXTMODE2") (class "Default")
      (node (ref "H2") (pin "15") (pinfunction "EXTMODE_15") (pintype "bidirectional"))
      (node (ref "P2") (pin "16") (pinfunction "PB2_16") (pintype "bidirectional"))
    )
    (net (code "28") (name "EXTMODE3") (class "Default")
      (node (ref "H3") (pin "15") (pinfunction "EXTMODE_15") (pintype "bidirectional"))
      (node (ref "P3") (pin "16") (pinfunction "PB2_16") (pintype "bidirectional"))
    )
    (net (code "29") (name "EXTMODE4") (class "Default")
      (node (ref "H4") (pin "15") (pinfunction "EXTMODE_15") (pintype "bidirectional"))
      (node (ref "P4") (pin "16") (pinfunction "PB2_16") (pintype "bidirectional"))
    )
    (net (code "30") (name "EXTMODE5") (class "Default")
      (node (ref "H5") (pin "15") (pinfunction "EXTMODE_15") (pintype "bidirectional"))
      (node (ref "P5") (pin "16") (pinfunction "PB2_16") (pintype "bidirectional"))
    )
    (net (code "31") (name "GND") (class "Default")
      (node (ref "C10") (pin "2") (pinfunction "2_2") (pintype "passive"))
      (node (ref "C10_1") (pin "1") (pinfunction "1_1") (pintype "passive"))
      (node (ref "C10_2") (pin "1") (pinfunction "1_1") (pintype "passive"))
      (node (ref "C10_3") (pin "1") (pinfunction "1_1") (pintype "passive"))
      (node (ref "C10_4") (pin "1") (pinfunction "1_1") (pintype "passive"))
      (node (ref "C10_5") (pin "1") (pinfunction "1_1") (pintype "passive"))
      (node (ref "C11_1") (pin "2") (pinfunction "2_2") (pintype "passive"))
      (node (ref "C11_2") (pin "2") (pinfunction "2_2") (pintype "passive"))
      (node (ref "C11_3") (pin "2") (pinfunction "2_2") (pintype "passive"))
      (node (ref "C11_4") (pin "2") (pinfunction "2_2") (pintype "passive"))
      (node (ref "C11_5") (pin "2") (pinfunction "2_2") (pintype "passive"))
      (node (ref "C12_1") (pin "1") (pinfunction "1_1") (pintype "passive"))
      (node (ref "C12_2") (pin "1") (pinfunction "1_1") (pintype "passive"))
      (node (ref "C12_3") (pin "1") (pinfunction "1_1") (pintype "passive"))
      (node (ref "C12_4") (pin "1") (pinfunction "1_1") (pintype "passive"))
      (node (ref "C12_5") (pin "1") (pinfunction "1_1") (pintype "passive"))
      (node (ref "C1_1") (pin "1") (pinfunction "1_1") (pintype "passive"))
      (node (ref "C1_2") (pin "1") (pinfunction "1_1") (pintype "passive"))
      (node (ref "C1_3") (pin "1") (pinfunction "1_1") (pintype "passive"))
      (node (ref "C1_4") (pin "1") (pinfunction "1_1") (pintype "passive"))
      (node (ref "C1_5") (pin "1") (pinfunction "1_1") (pintype "passive"))
      (node (ref "C1_6") (pin "1") (pinfunction "1_1") (pintype "passive"))
      (node (ref "C1_M") (pin "1") (pinfunction "1_1") (pintype "passive"))
      (node (ref "C2_1") (pin "1") (pinfunction "1_1") (pintype "passive"))
      (node (ref "C2_2") (pin "1") (pinfunction "1_1") (pintype "passive"))
      (node (ref "C2_3") (pin "1") (pinfunction "1_1") (pintype "passive"))
      (node (ref "C2_4") (pin "1") (pinfunction "1_1") (pintype "passive"))
      (node (ref "C2_5") (pin "1") (pinfunction "1_1") (pintype "passive"))
      (node (ref "C2_6") (pin "1") (pinfunction "1_1") (pintype "passive"))
      (node (ref "C2_M") (pin "1") (pinfunction "1_1") (pintype "passive"))
      (node (ref "C3_1") (pin "1") (pinfunction "1_1") (pintype "passive"))
      (node (ref "C3_2") (pin "1") (pinfunction "1_1") (pintype "passive"))
      (node (ref "C3_3") (pin "1") (pinfunction "1_1") (pintype "passive"))
      (node (ref "C3_4") (pin "1") (pinfunction "1_1") (pintype "passive"))
      (node (ref "C3_5") (pin "1") (pinfunction "1_1") (pintype "passive"))
      (node (ref "C3_6") (pin "1") (pinfunction "1_1") (pintype "passive"))
      (node (ref "C3_M") (pin "1") (pinfunction "1_1") (pintype "passive"))
      (node (ref "C4_1") (pin "2") (pinfunction "2_2") (pintype "passive"))
      (node (ref "C4_2") (pin "2") (pinfunction "2_2") (pintype "passive"))
      (node (ref "C4_3") (pin "2") (pinfunction "2_2") (pintype "passive"))
      (node (ref "C4_4") (pin "2") (pinfunction "2_2") (pintype "passive"))
      (node (ref "C4_5") (pin "2") (pinfunction "2_2") (pintype "passive"))
      (node (ref "C4_6") (pin "2") (pinfunction "2_2") (pintype "passive"))
      (node (ref "C4_M") (pin "2") (pinfunction "2_2") (pintype "passive"))
      (node (ref "C5_1") (pin "2") (pinfunction "2_2") (pintype "passive"))
      (node (ref "C5_2") (pin "2") (pinfunction "2_2") (pintype "passive"))
      (node (ref "C5_3") (pin "2") (pinfunction "2_2") (pintype "passive"))
      (node (ref "C5_4") (pin "2") (pinfunction "2_2") (pintype "passive"))
      (node (ref "C5_5") (pin "2") (pinfunction "2_2") (pintype "passive"))
      (node (ref "C5_6") (pin "2") (pinfunction "2_2") (pintype "passive"))
      (node (ref "C5_M") (pin "2") (pinfunction "2_2") (pintype "passive"))
      (node (ref "C7_1") (pin "2") (pinfunction "2_2") (pintype "passive"))
      (node (ref "C7_2") (pin "2") (pinfunction "2_2") (pintype "passive"))
      (node (ref "C7_3") (pin "2") (pinfunction "2_2") (pintype "passive"))
      (node (ref "C7_4") (pin "2") (pinfunction "2_2") (pintype "passive"))
      (node (ref "C7_5") (pin "2") (pinfunction "2_2") (pintype "passive"))
      (node (ref "C8_1") (pin "2") (pinfunction "2_2") (pintype "passive"))
      (node (ref "C8_2") (pin "2") (pinfunction "2_2") (pintype "passive"))
      (node (ref "C8_3") (pin "2") (pinfunction "2_2") (pintype "passive"))
      (node (ref "C8_4") (pin "2") (pinfunction "2_2") (pintype "passive"))
      (node (ref "C8_5") (pin "2") (pinfunction "2_2") (pintype "passive"))
      (node (ref "C9_1") (pin "2") (pinfunction "2_2") (pintype "passive"))
      (node (ref "C9_2") (pin "2") (pinfunction "2_2") (pintype "passive"))
      (node (ref "C9_3") (pin "2") (pinfunction "2_2") (pintype "passive"))
      (node (ref "C9_4") (pin "2") (pinfunction "2_2") (pintype "passive"))
      (node (ref "C9_5") (pin "2") (pinfunction "2_2") (pintype "passive"))
      (node (ref "CV3") (pin "2") (pinfunction "2_2") (pintype "passive"))
      (node (ref "CV4") (pin "2") (pinfunction "2_2") (pintype "passive"))
      (node (ref "E1") (pin "5") (pinfunction "5_5") (pintype "passive"))
      (node (ref "E2") (pin "5") (pinfunction "5_5") (pintype "passive"))
      (node (ref "E3") (pin "5") (pinfunction "5_5") (pintype "passive"))
      (node (ref "E4") (pin "5") (pinfunction "5_5") (pintype "passive"))
      (node (ref "E5") (pin "5") (pinfunction "5_5") (pintype "passive"))
      (node (ref "H1") (pin "18") (pinfunction "GND4_18") (pintype "bidirectional"))
      (node (ref "H1") (pin "19") (pinfunction "GND5_19") (pintype "bidirectional"))
      (node (ref "H1") (pin "5") (pinfunction "GND_5") (pintype "bidirectional"))
      (node (ref "H1") (pin "6") (pinfunction "GND1_6") (pintype "bidirectional"))
      (node (ref "H1") (pin "7") (pinfunction "GND2_7") (pintype "bidirectional"))
      (node (ref "H1") (pin "8") (pinfunction "GND3_8") (pintype "bidirectional"))
      (node (ref "H2") (pin "18") (pinfunction "GND4_18") (pintype "bidirectional"))
      (node (ref "H2") (pin "19") (pinfunction "GND5_19") (pintype "bidirectional"))
      (node (ref "H2") (pin "5") (pinfunction "GND_5") (pintype "bidirectional"))
      (node (ref "H2") (pin "6") (pinfunction "GND1_6") (pintype "bidirectional"))
      (node (ref "H2") (pin "7") (pinfunction "GND2_7") (pintype "bidirectional"))
      (node (ref "H2") (pin "8") (pinfunction "GND3_8") (pintype "bidirectional"))
      (node (ref "H3") (pin "18") (pinfunction "GND4_18") (pintype "bidirectional"))
      (node (ref "H3") (pin "19") (pinfunction "GND5_19") (pintype "bidirectional"))
      (node (ref "H3") (pin "5") (pinfunction "GND_5") (pintype "bidirectional"))
      (node (ref "H3") (pin "6") (pinfunction "GND1_6") (pintype "bidirectional"))
      (node (ref "H3") (pin "7") (pinfunction "GND2_7") (pintype "bidirectional"))
      (node (ref "H3") (pin "8") (pinfunction "GND3_8") (pintype "bidirectional"))
      (node (ref "H4") (pin "18") (pinfunction "GND4_18") (pintype "bidirectional"))
      (node (ref "H4") (pin "19") (pinfunction "GND5_19") (pintype "bidirectional"))
      (node (ref "H4") (pin "5") (pinfunction "GND_5") (pintype "bidirectional"))
      (node (ref "H4") (pin "6") (pinfunction "GND1_6") (pintype "bidirectional"))
      (node (ref "H4") (pin "7") (pinfunction "GND2_7") (pintype "bidirectional"))
      (node (ref "H4") (pin "8") (pinfunction "GND3_8") (pintype "bidirectional"))
      (node (ref "H5") (pin "18") (pinfunction "GND4_18") (pintype "bidirectional"))
      (node (ref "H5") (pin "19") (pinfunction "GND5_19") (pintype "bidirectional"))
      (node (ref "H5") (pin "5") (pinfunction "GND_5") (pintype "bidirectional"))
      (node (ref "H5") (pin "6") (pinfunction "GND1_6") (pintype "bidirectional"))
      (node (ref "H5") (pin "7") (pinfunction "GND2_7") (pintype "bidirectional"))
      (node (ref "H5") (pin "8") (pinfunction "GND3_8") (pintype "bidirectional"))
      (node (ref "J6") (pin "P$1") (pinfunction "1_P$1") (pintype "bidirectional"))
      (node (ref "JP1") (pin "2") (pinfunction "2_2") (pintype "passive"))
      (node (ref "JP14") (pin "1") (pinfunction "1_1") (pintype "passive"))
      (node (ref "JP15") (pin "1") (pinfunction "1_1") (pintype "passive"))
      (node (ref "LED1") (pin "C") (pinfunction "C_C") (pintype "passive"))
      (node (ref "LED10") (pin "C") (pinfunction "C_C") (pintype "passive"))
      (node (ref "LED11") (pin "C") (pinfunction "C_C") (pintype "passive"))
      (node (ref "LED12") (pin "C") (pinfunction "C_C") (pintype "passive"))
      (node (ref "LED13") (pin "C") (pinfunction "C_C") (pintype "passive"))
      (node (ref "LED14") (pin "C") (pinfunction "C_C") (pintype "passive"))
      (node (ref "LED15") (pin "C") (pinfunction "C_C") (pintype "passive"))
      (node (ref "LED16") (pin "C") (pinfunction "C_C") (pintype "passive"))
      (node (ref "LED17") (pin "C") (pinfunction "C_C") (pintype "passive"))
      (node (ref "LED18") (pin "C") (pinfunction "C_C") (pintype "passive"))
      (node (ref "LED2") (pin "C") (pinfunction "C_C") (pintype "passive"))
      (node (ref "LED21") (pin "C") (pinfunction "C_C") (pintype "passive"))
      (node (ref "LED3") (pin "C") (pinfunction "C_C") (pintype "passive"))
      (node (ref "LED4") (pin "C") (pinfunction "C_C") (pintype "passive"))
      (node (ref "LED5") (pin "C") (pinfunction "C_C") (pintype "passive"))
      (node (ref "LED6") (pin "C") (pinfunction "C_C") (pintype "passive"))
      (node (ref "LED7") (pin "C") (pinfunction "C_C") (pintype "passive"))
      (node (ref "LED8") (pin "C") (pinfunction "C_C") (pintype "passive"))
      (node (ref "LED9") (pin "C") (pinfunction "C_C") (pintype "passive"))
      (node (ref "MD") (pin "1") (pinfunction "1_1") (pintype "passive"))
      (node (ref "MP") (pin "22") (pinfunction "GND1_22") (pintype "bidirectional"))
      (node (ref "MP") (pin "8") (pinfunction "GND_8") (pintype "bidirectional"))
      (node (ref "MS") (pin "P$1") (pinfunction "1_P$1") (pintype "bidirectional"))
      (node (ref "O6") (pin "1") (pinfunction "1_1") (pintype "passive"))
      (node (ref "P1") (pin "22") (pinfunction "GND1_22") (pintype "bidirectional"))
      (node (ref "P1") (pin "8") (pinfunction "GND_8") (pintype "bidirectional"))
      (node (ref "P2") (pin "22") (pinfunction "GND1_22") (pintype "bidirectional"))
      (node (ref "P2") (pin "8") (pinfunction "GND_8") (pintype "bidirectional"))
      (node (ref "P3") (pin "22") (pinfunction "GND1_22") (pintype "bidirectional"))
      (node (ref "P3") (pin "8") (pinfunction "GND_8") (pintype "bidirectional"))
      (node (ref "P4") (pin "22") (pinfunction "GND1_22") (pintype "bidirectional"))
      (node (ref "P4") (pin "8") (pinfunction "GND_8") (pintype "bidirectional"))
      (node (ref "P5") (pin "22") (pinfunction "GND1_22") (pintype "bidirectional"))
      (node (ref "P5") (pin "8") (pinfunction "GND_8") (pintype "bidirectional"))
      (node (ref "P6") (pin "22") (pinfunction "GND1_22") (pintype "bidirectional"))
      (node (ref "P6") (pin "8") (pinfunction "GND_8") (pintype "bidirectional"))
      (node (ref "Q1") (pin "3") (pinfunction "S_3") (pintype "passive"))
      (node (ref "Q2") (pin "3") (pinfunction "S_3") (pintype "passive"))
      (node (ref "Q3") (pin "4") (pinfunction "GND_4") (pintype "bidirectional"))
      (node (ref "Q4") (pin "3") (pinfunction "S_3") (pintype "passive"))
      (node (ref "Q5") (pin "2") (pinfunction "GND_2") (pintype "bidirectional"))
      (node (ref "R28") (pin "1") (pinfunction "1_1") (pintype "passive"))
      (node (ref "R29") (pin "1") (pinfunction "1_1") (pintype "passive"))
      (node (ref "R3") (pin "P$1") (pinfunction "1_P$1") (pintype "passive"))
      (node (ref "R30") (pin "1") (pinfunction "1_1") (pintype "passive"))
      (node (ref "R31") (pin "1") (pinfunction "1_1") (pintype "passive"))
      (node (ref "R32") (pin "1") (pinfunction "1_1") (pintype "passive"))
      (node (ref "R6") (pin "P$1") (pinfunction "1_P$1") (pintype "passive"))
      (node (ref "R6_1") (pin "2") (pinfunction "2_2") (pintype "passive"))
      (node (ref "R6_2") (pin "2") (pinfunction "2_2") (pintype "passive"))
      (node (ref "R6_3") (pin "2") (pinfunction "2_2") (pintype "passive"))
      (node (ref "R6_4") (pin "2") (pinfunction "2_2") (pintype "passive"))
      (node (ref "R6_5") (pin "2") (pinfunction "2_2") (pintype "passive"))
      (node (ref "R7") (pin "P$1") (pinfunction "1_P$1") (pintype "passive"))
      (node (ref "R7_1") (pin "2") (pinfunction "2_2") (pintype "passive"))
      (node (ref "R7_2") (pin "2") (pinfunction "2_2") (pintype "passive"))
      (node (ref "R7_3") (pin "2") (pinfunction "2_2") (pintype "passive"))
      (node (ref "R7_4") (pin "2") (pinfunction "2_2") (pintype "passive"))
      (node (ref "R7_5") (pin "2") (pinfunction "2_2") (pintype "passive"))
      (node (ref "S1") (pin "P$1") (pinfunction "1_P$1") (pintype "bidirectional"))
      (node (ref "S2") (pin "P$1") (pinfunction "1_P$1") (pintype "bidirectional"))
      (node (ref "S3") (pin "P$1") (pinfunction "1_P$1") (pintype "bidirectional"))
      (node (ref "S4") (pin "P$1") (pinfunction "1_P$1") (pintype "bidirectional"))
      (node (ref "S5") (pin "P$1") (pinfunction "1_P$1") (pintype "bidirectional"))
      (node (ref "SJ1") (pin "1") (pinfunction "1_1") (pintype "passive"))
      (node (ref "U$26") (pin "5") (pinfunction "GND_5") (pintype "bidirectional"))
    )
    (net (code "32") (name "INTERRUPT1_1") (class "Default")
      (node (ref "E1") (pin "2") (pinfunction "2_2") (pintype "passive"))
      (node (ref "P1") (pin "5") (pinfunction "PD3_5") (pintype "bidirectional"))
      (node (ref "R9_1") (pin "1") (pinfunction "1_1") (pintype "passive"))
    )
    (net (code "33") (name "INTERRUPT1_2") (class "Default")
      (node (ref "E2") (pin "2") (pinfunction "2_2") (pintype "passive"))
      (node (ref "P2") (pin "5") (pinfunction "PD3_5") (pintype "bidirectional"))
      (node (ref "R9_2") (pin "1") (pinfunction "1_1") (pintype "passive"))
    )
    (net (code "34") (name "INTERRUPT1_3") (class "Default")
      (node (ref "E3") (pin "2") (pinfunction "2_2") (pintype "passive"))
      (node (ref "P3") (pin "5") (pinfunction "PD3_5") (pintype "bidirectional"))
      (node (ref "R9_3") (pin "1") (pinfunction "1_1") (pintype "passive"))
    )
    (net (code "35") (name "INTERRUPT1_4") (class "Default")
      (node (ref "E4") (pin "2") (pinfunction "2_2") (pintype "passive"))
      (node (ref "P4") (pin "5") (pinfunction "PD3_5") (pintype "bidirectional"))
      (node (ref "R9_4") (pin "1") (pinfunction "1_1") (pintype "passive"))
    )
    (net (code "36") (name "INTERRUPT1_5") (class "Default")
      (node (ref "E5") (pin "2") (pinfunction "2_2") (pintype "passive"))
      (node (ref "P5") (pin "5") (pinfunction "PD3_5") (pintype "bidirectional"))
      (node (ref "R9_5") (pin "1") (pinfunction "1_1") (pintype "passive"))
    )
    (net (code "37") (name "INTERRUPT2_1") (class "Default")
      (node (ref "E1") (pin "1") (pinfunction "1_1") (pintype "passive"))
      (node (ref "P1") (pin "4") (pinfunction "PD2_4") (pintype "bidirectional"))
    )
    (net (code "38") (name "INTERRUPT2_2") (class "Default")
      (node (ref "E2") (pin "1") (pinfunction "1_1") (pintype "passive"))
      (node (ref "P2") (pin "4") (pinfunction "PD2_4") (pintype "bidirectional"))
    )
    (net (code "39") (name "INTERRUPT2_3") (class "Default")
      (node (ref "E3") (pin "1") (pinfunction "1_1") (pintype "passive"))
      (node (ref "P3") (pin "4") (pinfunction "PD2_4") (pintype "bidirectional"))
    )
    (net (code "40") (name "INTERRUPT2_4") (class "Default")
      (node (ref "E4") (pin "1") (pinfunction "1_1") (pintype "passive"))
      (node (ref "P4") (pin "4") (pinfunction "PD2_4") (pintype "bidirectional"))
    )
    (net (code "41") (name "INTERRUPT2_5") (class "Default")
      (node (ref "E5") (pin "1") (pinfunction "1_1") (pintype "passive"))
      (node (ref "P5") (pin "4") (pinfunction "PD2_4") (pintype "bidirectional"))
    )
    (net (code "42") (name "ISENSE1") (class "Default")
      (node (ref "C9_1") (pin "1") (pinfunction "1_1") (pintype "passive"))
      (node (ref "H1") (pin "17") (pinfunction "SENSE_17") (pintype "bidirectional"))
      (node (ref "P1") (pin "26") (pinfunction "PC3_26") (pintype "bidirectional"))
      (node (ref "R7_1") (pin "1") (pinfunction "1_1") (pintype "passive"))
    )
    (net (code "43") (name "ISENSE2") (class "Default")
      (node (ref "C9_2") (pin "1") (pinfunction "1_1") (pintype "passive"))
      (node (ref "H2") (pin "17") (pinfunction "SENSE_17") (pintype "bidirectional"))
      (node (ref "P2") (pin "26") (pinfunction "PC3_26") (pintype "bidirectional"))
      (node (ref "R7_2") (pin "1") (pinfunction "1_1") (pintype "passive"))
    )
    (net (code "44") (name "ISENSE3") (class "Default")
      (node (ref "C9_3") (pin "1") (pinfunction "1_1") (pintype "passive"))
      (node (ref "H3") (pin "17") (pinfunction "SENSE_17") (pintype "bidirectional"))
      (node (ref "P3") (pin "26") (pinfunction "PC3_26") (pintype "bidirectional"))
      (node (ref "R7_3") (pin "1") (pinfunction "1_1") (pintype "passive"))
    )
    (net (code "45") (name "ISENSE4") (class "Default")
      (node (ref "C9_4") (pin "1") (pinfunction "1_1") (pintype "passive"))
      (node (ref "H4") (pin "17") (pinfunction "SENSE_17") (pintype "bidirectional"))
      (node (ref "P4") (pin "26") (pinfunction "PC3_26") (pintype "bidirectional"))
      (node (ref "R7_4") (pin "1") (pinfunction "1_1") (pintype "passive"))
    )
    (net (code "46") (name "ISENSE5") (class "Default")
      (node (ref "C9_5") (pin "1") (pinfunction "1_1") (pintype "passive"))
      (node (ref "H5") (pin "17") (pinfunction "SENSE_17") (pintype "bidirectional"))
      (node (ref "P5") (pin "26") (pinfunction "PC3_26") (pintype "bidirectional"))
      (node (ref "R7_5") (pin "1") (pinfunction "1_1") (pintype "passive"))
    )
    (net (code "47") (name "LED1_1") (class "Default")
      (node (ref "P1") (pin "12") (pinfunction "PD6_12") (pintype "bidirectional"))
      (node (ref "R8") (pin "2") (pinfunction "2_2") (pintype "passive"))
    )
    (net (code "48") (name "LED1_2") (class "Default")
      (node (ref "P2") (pin "12") (pinfunction "PD6_12") (pintype "bidirectional"))
      (node (ref "R12") (pin "2") (pinfunction "2_2") (pintype "passive"))
    )
    (net (code "49") (name "LED1_3") (class "Default")
      (node (ref "P3") (pin "12") (pinfunction "PD6_12") (pintype "bidirectional"))
      (node (ref "R15") (pin "2") (pinfunction "2_2") (pintype "passive"))
    )
    (net (code "50") (name "LED1_4") (class "Default")
      (node (ref "P4") (pin "12") (pinfunction "PD6_12") (pintype "bidirectional"))
      (node (ref "R18") (pin "2") (pinfunction "2_2") (pintype "passive"))
    )
    (net (code "51") (name "LED1_5") (class "Default")
      (node (ref "P5") (pin "12") (pinfunction "PD6_12") (pintype "bidirectional"))
      (node (ref "R21") (pin "2") (pinfunction "2_2") (pintype "passive"))
    )
    (net (code "52") (name "LED1_6") (class "Default")
      (node (ref "P6") (pin "12") (pinfunction "PD6_12") (pintype "bidirectional"))
      (node (ref "R24") (pin "2") (pinfunction "2_2") (pintype "passive"))
    )
    (net (code "53") (name "LED2_1") (class "Default")
      (node (ref "P1") (pin "13") (pinfunction "PD7_13") (pintype "bidirectional"))
      (node (ref "R9") (pin "2") (pinfunction "2_2") (pintype "passive"))
    )
    (net (code "54") (name "LED2_2") (class "Default")
      (node (ref "P2") (pin "13") (pinfunction "PD7_13") (pintype "bidirectional"))
      (node (ref "R13") (pin "2") (pinfunction "2_2") (pintype "passive"))
    )
    (net (code "55") (name "LED2_3") (class "Default")
      (node (ref "P3") (pin "13") (pinfunction "PD7_13") (pintype "bidirectional"))
      (node (ref "R16") (pin "2") (pinfunction "2_2") (pintype "passive"))
    )
    (net (code "56") (name "LED2_4") (class "Default")
      (node (ref "P4") (pin "13") (pinfunction "PD7_13") (pintype "bidirectional"))
      (node (ref "R19") (pin "2") (pinfunction "2_2") (pintype "passive"))
    )
    (net (code "57") (name "LED2_5") (class "Default")
      (node (ref "P5") (pin "13") (pinfunction "PD7_13") (pintype "bidirectional"))
      (node (ref "R22") (pin "2") (pinfunction "2_2") (pintype "passive"))
    )
    (net (code "58") (name "LED2_6") (class "Default")
      (node (ref "P6") (pin "13") (pinfunction "PD7_13") (pintype "bidirectional"))
      (node (ref "R25") (pin "2") (pinfunction "2_2") (pintype "passive"))
    )
    (net (code "59") (name "N$15") (class "Default")
      (node (ref "P1") (pin "1") (pinfunction "PC6_1") (pintype "bidirectional"))
      (node (ref "R11") (pin "2") (pinfunction "2_2") (pintype "passive"))
      (node (ref "R1_1") (pin "1") (pinfunction "1_1") (pintype "passive"))
      (node (ref "S1") (pin "P$2") (pinfunction "2_P$2") (pintype "bidirectional"))
    )
    (net (code "60") (name "N$30") (class "Default")
      (node (ref "P2") (pin "1") (pinfunction "PC6_1") (pintype "bidirectional"))
      (node (ref "R14") (pin "2") (pinfunction "2_2") (pintype "passive"))
      (node (ref "R1_2") (pin "1") (pinfunction "1_1") (pintype "passive"))
      (node (ref "S2") (pin "P$2") (pinfunction "2_P$2") (pintype "bidirectional"))
    )
    (net (code "61") (name "N$43") (class "Default")
      (node (ref "P3") (pin "1") (pinfunction "PC6_1") (pintype "bidirectional"))
      (node (ref "R17") (pin "2") (pinfunction "2_2") (pintype "passive"))
      (node (ref "R1_3") (pin "1") (pinfunction "1_1") (pintype "passive"))
      (node (ref "S3") (pin "P$2") (pinfunction "2_P$2") (pintype "bidirectional"))
    )
    (net (code "62") (name "N$56") (class "Default")
      (node (ref "P4") (pin "1") (pinfunction "PC6_1") (pintype "bidirectional"))
      (node (ref "R1_4") (pin "1") (pinfunction "1_1") (pintype "passive"))
      (node (ref "R20") (pin "2") (pinfunction "2_2") (pintype "passive"))
      (node (ref "S4") (pin "P$2") (pinfunction "2_P$2") (pintype "bidirectional"))
    )
    (net (code "63") (name "N$69") (class "Default")
      (node (ref "P5") (pin "1") (pinfunction "PC6_1") (pintype "bidirectional"))
      (node (ref "R1_5") (pin "1") (pinfunction "1_1") (pintype "passive"))
      (node (ref "R23") (pin "2") (pinfunction "2_2") (pintype "passive"))
      (node (ref "S5") (pin "P$2") (pinfunction "2_P$2") (pintype "bidirectional"))
    )
    (net (code "64") (name "N$88") (class "Default")
      (node (ref "MP") (pin "1") (pinfunction "PC6_1") (pintype "bidirectional"))
      (node (ref "MS") (pin "P$2") (pinfunction "2_P$2") (pintype "bidirectional"))
      (node (ref "R1_M") (pin "1") (pinfunction "1_1") (pintype "passive"))
      (node (ref "R27") (pin "2") (pinfunction "2_2") (pintype "passive"))
    )
    (net (code "65") (name "Net-(E1-Pad3)") (class "Default")
      (node (ref "E1") (pin "3") (pinfunction "3_3") (pintype "passive"))
      (node (ref "R8_1") (pin "1") (pinfunction "1_1") (pintype "passive"))
    )
    (net (code "66") (name "Net-(E2-Pad3)") (class "Default")
      (node (ref "E2") (pin "3") (pinfunction "3_3") (pintype "passive"))
      (node (ref "R8_2") (pin "1") (pinfunction "1_1") (pintype "passive"))
    )
    (net (code "67") (name "Net-(E3-Pad3)") (class "Default")
      (node (ref "E3") (pin "3") (pinfunction "3_3") (pintype "passive"))
      (node (ref "R8_3") (pin "1") (pinfunction "1_1") (pintype "passive"))
    )
    (net (code "68") (name "Net-(E4-Pad3)") (class "Default")
      (node (ref "E4") (pin "3") (pinfunction "3_3") (pintype "passive"))
      (node (ref "R8_4") (pin "1") (pinfunction "1_1") (pintype "passive"))
    )
    (net (code "69") (name "Net-(E5-Pad3)") (class "Default")
      (node (ref "E5") (pin "3") (pinfunction "3_3") (pintype "passive"))
      (node (ref "R8_5") (pin "1") (pinfunction "1_1") (pintype "passive"))
    )
    (net (code "70") (name "Net-(H1-CP)") (class "Default")
      (node (ref "C12_1") (pin "2") (pinfunction "2_2") (pintype "passive"))
      (node (ref "H1") (pin "24") (pinfunction "CP_24") (pintype "bidirectional"))
    )
    (net (code "71") (name "Net-(H1-CP1)") (class "Default")
      (node (ref "C6_1") (pin "2") (pinfunction "2_2") (pintype "passive"))
      (node (ref "H1") (pin "2") (pinfunction "CP1_2") (pintype "bidirectional"))
    )
    (net (code "72") (name "Net-(H1-CP2)") (class "Default")
      (node (ref "C6_1") (pin "1") (pinfunction "1_1") (pintype "passive"))
      (node (ref "H1") (pin "1") (pinfunction "CP2_1") (pintype "bidirectional"))
    )
    (net (code "73") (name "Net-(H1-REF)") (class "Default")
      (node (ref "C8_1") (pin "1") (pinfunction "1_1") (pintype "passive"))
      (node (ref "H1") (pin "14") (pinfunction "REF_14") (pintype "bidirectional"))
      (node (ref "R5_1") (pin "1") (pinfunction "1_1") (pintype "passive"))
      (node (ref "R6_1") (pin "1") (pinfunction "1_1") (pintype "passive"))
    )
    (net (code "74") (name "Net-(H1-ROSC)") (class "Default")
      (node (ref "H1") (pin "4") (pinfunction "ROSC_4") (pintype "bidirectional"))
      (node (ref "R4_1") (pin "2") (pinfunction "2_2") (pintype "passive"))
    )
    (net (code "75") (name "Net-(H1-VREG)") (class "Default")
      (node (ref "C11_1") (pin "1") (pinfunction "1_1") (pintype "passive"))
      (node (ref "H1") (pin "23") (pinfunction "VREG_23") (pintype "bidirectional"))
    )
    (net (code "76") (name "Net-(H2-CP)") (class "Default")
      (node (ref "C12_2") (pin "2") (pinfunction "2_2") (pintype "passive"))
      (node (ref "H2") (pin "24") (pinfunction "CP_24") (pintype "bidirectional"))
    )
    (net (code "77") (name "Net-(H2-CP1)") (class "Default")
      (node (ref "C6_2") (pin "2") (pinfunction "2_2") (pintype "passive"))
      (node (ref "H2") (pin "2") (pinfunction "CP1_2") (pintype "bidirectional"))
    )
    (net (code "78") (name "Net-(H2-CP2)") (class "Default")
      (node (ref "C6_2") (pin "1") (pinfunction "1_1") (pintype "passive"))
      (node (ref "H2") (pin "1") (pinfunction "CP2_1") (pintype "bidirectional"))
    )
    (net (code "79") (name "Net-(H2-REF)") (class "Default")
      (node (ref "C8_2") (pin "1") (pinfunction "1_1") (pintype "passive"))
      (node (ref "H2") (pin "14") (pinfunction "REF_14") (pintype "bidirectional"))
      (node (ref "R5_2") (pin "1") (pinfunction "1_1") (pintype "passive"))
      (node (ref "R6_2") (pin "1") (pinfunction "1_1") (pintype "passive"))
    )
    (net (code "80") (name "Net-(H2-ROSC)") (class "Default")
      (node (ref "H2") (pin "4") (pinfunction "ROSC_4") (pintype "bidirectional"))
      (node (ref "R4_2") (pin "2") (pinfunction "2_2") (pintype "passive"))
    )
    (net (code "81") (name "Net-(H2-VREG)") (class "Default")
      (node (ref "C11_2") (pin "1") (pinfunction "1_1") (pintype "passive"))
      (node (ref "H2") (pin "23") (pinfunction "VREG_23") (pintype "bidirectional"))
    )
    (net (code "82") (name "Net-(H3-CP)") (class "Default")
      (node (ref "C12_3") (pin "2") (pinfunction "2_2") (pintype "passive"))
      (node (ref "H3") (pin "24") (pinfunction "CP_24") (pintype "bidirectional"))
    )
    (net (code "83") (name "Net-(H3-CP1)") (class "Default")
      (node (ref "C6_3") (pin "2") (pinfunction "2_2") (pintype "passive"))
      (node (ref "H3") (pin "2") (pinfunction "CP1_2") (pintype "bidirectional"))
    )
    (net (code "84") (name "Net-(H3-CP2)") (class "Default")
      (node (ref "C6_3") (pin "1") (pinfunction "1_1") (pintype "passive"))
      (node (ref "H3") (pin "1") (pinfunction "CP2_1") (pintype "bidirectional"))
    )
    (net (code "85") (name "Net-(H3-REF)") (class "Default")
      (node (ref "C8_3") (pin "1") (pinfunction "1_1") (pintype "passive"))
      (node (ref "H3") (pin "14") (pinfunction "REF_14") (pintype "bidirectional"))
      (node (ref "R5_3") (pin "1") (pinfunction "1_1") (pintype "passive"))
      (node (ref "R6_3") (pin "1") (pinfunction "1_1") (pintype "passive"))
    )
    (net (code "86") (name "Net-(H3-ROSC)") (class "Default")
      (node (ref "H3") (pin "4") (pinfunction "ROSC_4") (pintype "bidirectional"))
      (node (ref "R4_3") (pin "2") (pinfunction "2_2") (pintype "passive"))
    )
    (net (code "87") (name "Net-(H3-VREG)") (class "Default")
      (node (ref "C11_3") (pin "1") (pinfunction "1_1") (pintype "passive"))
      (node (ref "H3") (pin "23") (pinfunction "VREG_23") (pintype "bidirectional"))
    )
    (net (code "88") (name "Net-(H4-CP)") (class "Default")
      (node (ref "C12_4") (pin "2") (pinfunction "2_2") (pintype "passive"))
      (node (ref "H4") (pin "24") (pinfunction "CP_24") (pintype "bidirectional"))
    )
    (net (code "89") (name "Net-(H4-CP1)") (class "Default")
      (node (ref "C6_4") (pin "2") (pinfunction "2_2") (pintype "passive"))
      (node (ref "H4") (pin "2") (pinfunction "CP1_2") (pintype "bidirectional"))
    )
    (net (code "90") (name "Net-(H4-CP2)") (class "Default")
      (node (ref "C6_4") (pin "1") (pinfunction "1_1") (pintype "passive"))
      (node (ref "H4") (pin "1") (pinfunction "CP2_1") (pintype "bidirectional"))
    )
    (net (code "91") (name "Net-(H4-REF)") (class "Default")
      (node (ref "C8_4") (pin "1") (pinfunction "1_1") (pintype "passive"))
      (node (ref "H4") (pin "14") (pinfunction "REF_14") (pintype "bidirectional"))
      (node (ref "R5_4") (pin "1") (pinfunction "1_1") (pintype "passive"))
      (node (ref "R6_4") (pin "1") (pinfunction "1_1") (pintype "passive"))
    )
    (net (code "92") (name "Net-(H4-ROSC)") (class "Default")
      (node (ref "H4") (pin "4") (pinfunction "ROSC_4") (pintype "bidirectional"))
      (node (ref "R4_4") (pin "2") (pinfunction "2_2") (pintype "passive"))
    )
    (net (code "93") (name "Net-(H4-VREG)") (class "Default")
      (node (ref "C11_4") (pin "1") (pinfunction "1_1") (pintype "passive"))
      (node (ref "H4") (pin "23") (pinfunction "VREG_23") (pintype "bidirectional"))
    )
    (net (code "94") (name "Net-(H5-CP)") (class "Default")
      (node (ref "C12_5") (pin "2") (pinfunction "2_2") (pintype "passive"))
      (node (ref "H5") (pin "24") (pinfunction "CP_24") (pintype "bidirectional"))
    )
    (net (code "95") (name "Net-(H5-CP1)") (class "Default")
      (node (ref "C6_5") (pin "2") (pinfunction "2_2") (pintype "passive"))
      (node (ref "H5") (pin "2") (pinfunction "CP1_2") (pintype "bidirectional"))
    )
    (net (code "96") (name "Net-(H5-CP2)") (class "Default")
      (node (ref "C6_5") (pin "1") (pinfunction "1_1") (pintype "passive"))
      (node (ref "H5") (pin "1") (pinfunction "CP2_1") (pintype "bidirectional"))
    )
    (net (code "97") (name "Net-(H5-REF)") (class "Default")
      (node (ref "C8_5") (pin "1") (pinfunction "1_1") (pintype "passive"))
      (node (ref "H5") (pin "14") (pinfunction "REF_14") (pintype "bidirectional"))
      (node (ref "R5_5") (pin "1") (pinfunction "1_1") (pintype "passive"))
      (node (ref "R6_5") (pin "1") (pinfunction "1_1") (pintype "passive"))
    )
    (net (code "98") (name "Net-(H5-ROSC)") (class "Default")
      (node (ref "H5") (pin "4") (pinfunction "ROSC_4") (pintype "bidirectional"))
      (node (ref "R4_5") (pin "2") (pinfunction "2_2") (pintype "passive"))
    )
    (net (code "99") (name "Net-(H5-VREG)") (class "Default")
      (node (ref "C11_5") (pin "1") (pinfunction "1_1") (pintype "passive"))
      (node (ref "H5") (pin "23") (pinfunction "VREG_23") (pintype "bidirectional"))
    )
    (net (code "100") (name "Net-(LED1-PadA)") (class "Default")
      (node (ref "LED1") (pin "A") (pinfunction "A_A") (pintype "passive"))
      (node (ref "R11") (pin "1") (pinfunction "1_1") (pintype "passive"))
    )
    (net (code "101") (name "Net-(LED2-PadA)") (class "Default")
      (node (ref "LED2") (pin "A") (pinfunction "A_A") (pintype "passive"))
      (node (ref "R9") (pin "1") (pinfunction "1_1") (pintype "passive"))
    )
    (net (code "102") (name "Net-(LED3-PadA)") (class "Default")
      (node (ref "LED3") (pin "A") (pinfunction "A_A") (pintype "passive"))
      (node (ref "R8") (pin "1") (pinfunction "1_1") (pintype "passive"))
    )
    (net (code "103") (name "Net-(LED4-PadA)") (class "Default")
      (node (ref "LED4") (pin "A") (pinfunction "A_A") (pintype "passive"))
      (node (ref "R14") (pin "1") (pinfunction "1_1") (pintype "passive"))
    )
    (net (code "104") (name "Net-(LED5-PadA)") (class "Default")
      (node (ref "LED5") (pin "A") (pinfunction "A_A") (pintype "passive"))
      (node (ref "R13") (pin "1") (pinfunction "1_1") (pintype "passive"))
    )
    (net (code "105") (name "Net-(LED6-PadA)") (class "Default")
      (node (ref "LED6") (pin "A") (pinfunction "A_A") (pintype "passive"))
      (node (ref "R12") (pin "1") (pinfunction "1_1") (pintype "passive"))
    )
    (net (code "106") (name "Net-(LED7-PadA)") (class "Default")
      (node (ref "LED7") (pin "A") (pinfunction "A_A") (pintype "passive"))
      (node (ref "R17") (pin "1") (pinfunction "1_1") (pintype "passive"))
    )
    (net (code "107") (name "Net-(LED8-PadA)") (class "Default")
      (node (ref "LED8") (pin "A") (pinfunction "A_A") (pintype "passive"))
      (node (ref "R16") (pin "1") (pinfunction "1_1") (pintype "passive"))
    )
    (net (code "108") (name "Net-(LED9-PadA)") (class "Default")
      (node (ref "LED9") (pin "A") (pinfunction "A_A") (pintype "passive"))
      (node (ref "R15") (pin "1") (pinfunction "1_1") (pintype "passive"))
    )
    (net (code "109") (name "Net-(LED10-PadA)") (class "Default")
      (node (ref "LED10") (pin "A") (pinfunction "A_A") (pintype "passive"))
      (node (ref "R20") (pin "1") (pinfunction "1_1") (pintype "passive"))
    )
    (net (code "110") (name "Net-(LED11-PadA)") (class "Default")
      (node (ref "LED11") (pin "A") (pinfunction "A_A") (pintype "passive"))
      (node (ref "R19") (pin "1") (pinfunction "1_1") (pintype "passive"))
    )
    (net (code "111") (name "Net-(LED12-PadA)") (class "Default")
      (node (ref "LED12") (pin "A") (pinfunction "A_A") (pintype "passive"))
      (node (ref "R18") (pin "1") (pinfunction "1_1") (pintype "passive"))
    )
    (net (code "112") (name "Net-(LED13-PadA)") (class "Default")
      (node (ref "LED13") (pin "A") (pinfunction "A_A") (pintype "passive"))
      (node (ref "R23") (pin "1") (pinfunction "1_1") (pintype "passive"))
    )
    (net (code "113") (name "Net-(LED14-PadA)") (class "Default")
      (node (ref "LED14") (pin "A") (pinfunction "A_A") (pintype "passive"))
      (node (ref "R22") (pin "1") (pinfunction "1_1") (pintype "passive"))
    )
    (net (code "114") (name "Net-(LED15-PadA)") (class "Default")
      (node (ref "LED15") (pin "A") (pinfunction "A_A") (pintype "passive"))
      (node (ref "R21") (pin "1") (pinfunction "1_1") (pintype "passive"))
    )
    (net (code "115") (name "Net-(LED16-PadA)") (class "Default")
      (node (ref "LED16") (pin "A") (pinfunction "A_A") (pintype "passive"))
      (node (ref "R26") (pin "1") (pinfunction "1_1") (pintype "passive"))
    )
    (net (code "116") (name "Net-(LED17-PadA)") (class "Default")
      (node (ref "LED17") (pin "A") (pinfunction "A_A") (pintype "passive"))
      (node (ref "R25") (pin "1") (pinfunction "1_1") (pintype "passive"))
    )
    (net (code "117") (name "Net-(LED18-PadA)") (class "Default")
      (node (ref "LED18") (pin "A") (pinfunction "A_A") (pintype "passive"))
      (node (ref "R24") (pin "1") (pinfunction "1_1") (pintype "passive"))
    )
    (net (code "118") (name "Net-(LED21-PadA)") (class "Default")
      (node (ref "LED21") (pin "A") (pinfunction "A_A") (pintype "passive"))
      (node (ref "R27") (pin "1") (pinfunction "1_1") (pintype "passive"))
    )
    (net (code "119") (name "Net-(MP-AREF)") (class "Default")
      (node (ref "C5_M") (pin "1") (pinfunction "1_1") (pintype "passive"))
      (node (ref "MP") (pin "21") (pinfunction "AREF_21") (pintype "bidirectional"))
    )
    (net (code "120") (name "Net-(MP-XTAL1)") (class "Default")
      (node (ref "C2_M") (pin "2") (pinfunction "2_2") (pintype "passive"))
      (node (ref "MP") (pin "9") (pinfunction "XTAL1_9") (pintype "bidirectional"))
      (node (ref "MX") (pin "P$2") (pinfunction "2_P$2") (pintype "passive"))
    )
    (net (code "121") (name "Net-(MP-XTAL2)") (class "Default")
      (node (ref "C3_M") (pin "2") (pinfunction "2_2") (pintype "passive"))
      (node (ref "MP") (pin "10") (pinfunction "XTAL2_10") (pintype "bidirectional"))
      (node (ref "MX") (pin "P$1") (pinfunction "1_P$1") (pintype "passive"))
    )
    (net (code "122") (name "Net-(P1-AREF)") (class "Default")
      (node (ref "C5_1") (pin "1") (pinfunction "1_1") (pintype "passive"))
      (node (ref "P1") (pin "21") (pinfunction "AREF_21") (pintype "bidirectional"))
    )
    (net (code "123") (name "Net-(P1-XTAL1)") (class "Default")
      (node (ref "C2_1") (pin "2") (pinfunction "2_2") (pintype "passive"))
      (node (ref "P1") (pin "9") (pinfunction "XTAL1_9") (pintype "bidirectional"))
      (node (ref "X1") (pin "P$2") (pinfunction "2_P$2") (pintype "passive"))
    )
    (net (code "124") (name "Net-(P1-XTAL2)") (class "Default")
      (node (ref "C3_1") (pin "2") (pinfunction "2_2") (pintype "passive"))
      (node (ref "P1") (pin "10") (pinfunction "XTAL2_10") (pintype "bidirectional"))
      (node (ref "X1") (pin "P$1") (pinfunction "1_P$1") (pintype "passive"))
    )
    (net (code "125") (name "Net-(P2-AREF)") (class "Default")
      (node (ref "C5_2") (pin "1") (pinfunction "1_1") (pintype "passive"))
      (node (ref "P2") (pin "21") (pinfunction "AREF_21") (pintype "bidirectional"))
    )
    (net (code "126") (name "Net-(P2-XTAL1)") (class "Default")
      (node (ref "C2_2") (pin "2") (pinfunction "2_2") (pintype "passive"))
      (node (ref "P2") (pin "9") (pinfunction "XTAL1_9") (pintype "bidirectional"))
      (node (ref "X2") (pin "P$2") (pinfunction "2_P$2") (pintype "passive"))
    )
    (net (code "127") (name "Net-(P2-XTAL2)") (class "Default")
      (node (ref "C3_2") (pin "2") (pinfunction "2_2") (pintype "passive"))
      (node (ref "P2") (pin "10") (pinfunction "XTAL2_10") (pintype "bidirectional"))
      (node (ref "X2") (pin "P$1") (pinfunction "1_P$1") (pintype "passive"))
    )
    (net (code "128") (name "Net-(P3-AREF)") (class "Default")
      (node (ref "C5_3") (pin "1") (pinfunction "1_1") (pintype "passive"))
      (node (ref "P3") (pin "21") (pinfunction "AREF_21") (pintype "bidirectional"))
    )
    (net (code "129") (name "Net-(P3-XTAL1)") (class "Default")
      (node (ref "C2_3") (pin "2") (pinfunction "2_2") (pintype "passive"))
      (node (ref "P3") (pin "9") (pinfunction "XTAL1_9") (pintype "bidirectional"))
      (node (ref "X3") (pin "P$2") (pinfunction "2_P$2") (pintype "passive"))
    )
    (net (code "130") (name "Net-(P3-XTAL2)") (class "Default")
      (node (ref "C3_3") (pin "2") (pinfunction "2_2") (pintype "passive"))
      (node (ref "P3") (pin "10") (pinfunction "XTAL2_10") (pintype "bidirectional"))
      (node (ref "X3") (pin "P$1") (pinfunction "1_P$1") (pintype "passive"))
    )
    (net (code "131") (name "Net-(P4-AREF)") (class "Default")
      (node (ref "C5_4") (pin "1") (pinfunction "1_1") (pintype "passive"))
      (node (ref "P4") (pin "21") (pinfunction "AREF_21") (pintype "bidirectional"))
    )
    (net (code "132") (name "Net-(P4-XTAL1)") (class "Default")
      (node (ref "C2_4") (pin "2") (pinfunction "2_2") (pintype "passive"))
      (node (ref "P4") (pin "9") (pinfunction "XTAL1_9") (pintype "bidirectional"))
      (node (ref "X4") (pin "P$2") (pinfunction "2_P$2") (pintype "passive"))
    )
    (net (code "133") (name "Net-(P4-XTAL2)") (class "Default")
      (node (ref "C3_4") (pin "2") (pinfunction "2_2") (pintype "passive"))
      (node (ref "P4") (pin "10") (pinfunction "XTAL2_10") (pintype "bidirectional"))
      (node (ref "X4") (pin "P$1") (pinfunction "1_P$1") (pintype "passive"))
    )
    (net (code "134") (name "Net-(P5-AREF)") (class "Default")
      (node (ref "C5_5") (pin "1") (pinfunction "1_1") (pintype "passive"))
      (node (ref "P5") (pin "21") (pinfunction "AREF_21") (pintype "bidirectional"))
    )
    (net (code "135") (name "Net-(P5-XTAL1)") (class "Default")
      (node (ref "C2_5") (pin "2") (pinfunction "2_2") (pintype "passive"))
      (node (ref "P5") (pin "9") (pinfunction "XTAL1_9") (pintype "bidirectional"))
      (node (ref "X5") (pin "P$2") (pinfunction "2_P$2") (pintype "passive"))
    )
    (net (code "136") (name "Net-(P5-XTAL2)") (class "Default")
      (node (ref "C3_5") (pin "2") (pinfunction "2_2") (pintype "passive"))
      (node (ref "P5") (pin "10") (pinfunction "XTAL2_10") (pintype "bidirectional"))
      (node (ref "X5") (pin "P$1") (pinfunction "1_P$1") (pintype "passive"))
    )
    (net (code "137") (name "Net-(P6-AREF)") (class "Default")
      (node (ref "C5_6") (pin "1") (pinfunction "1_1") (pintype "passive"))
      (node (ref "P6") (pin "21") (pinfunction "AREF_21") (pintype "bidirectional"))
    )
    (net (code "138") (name "Net-(P6-XTAL1)") (class "Default")
      (node (ref "C2_6") (pin "2") (pinfunction "2_2") (pintype "passive"))
      (node (ref "P6") (pin "9") (pinfunction "XTAL1_9") (pintype "bidirectional"))
      (node (ref "X6") (pin "P$2") (pinfunction "2_P$2") (pintype "passive"))
    )
    (net (code "139") (name "Net-(P6-XTAL2)") (class "Default")
      (node (ref "C3_6") (pin "2") (pinfunction "2_2") (pintype "passive"))
      (node (ref "P6") (pin "10") (pinfunction "XTAL2_10") (pintype "bidirectional"))
      (node (ref "X6") (pin "P$1") (pinfunction "1_P$1") (pintype "passive"))
    )
    (net (code "140") (name "Net-(Q3-A)") (class "Default")
      (node (ref "Q3") (pin "8") (pinfunction "A_8") (pintype "bidirectional"))
      (node (ref "R4") (pin "P$1") (pinfunction "1_P$1") (pintype "passive"))
      (node (ref "U$2") (pin "3") (pinfunction "3_3") (pintype "bidirectional"))
    )
    (net (code "141") (name "Net-(Q3-B)") (class "Default")
      (node (ref "Q3") (pin "7") (pinfunction "B_7") (pintype "bidirectional"))
      (node (ref "R4") (pin "P$2") (pinfunction "2_P$2") (pintype "passive"))
      (node (ref "U$2") (pin "6") (pinfunction "6_6") (pintype "bidirectional"))
    )
    (net (code "142") (name "Net-(Q3-Y)") (class "Default")
      (node (ref "Q3") (pin "5") (pinfunction "Y_5") (pintype "bidirectional"))
      (node (ref "R5") (pin "P$2") (pinfunction "2_P$2") (pintype "passive"))
      (node (ref "U$2") (pin "1") (pinfunction "1_1") (pintype "bidirectional"))
    )
    (net (code "143") (name "Net-(Q3-Z)") (class "Default")
      (node (ref "Q3") (pin "6") (pinfunction "Z_6") (pintype "bidirectional"))
      (node (ref "R5") (pin "P$1") (pinfunction "1_P$1") (pintype "passive"))
      (node (ref "U$2") (pin "2") (pinfunction "2_2") (pintype "bidirectional"))
    )
    (net (code "144") (name "Net-(SJ1-Pad2)") (class "Default")
      (node (ref "SJ1") (pin "2") (pinfunction "2_2") (pintype "passive"))
      (node (ref "U$2") (pin "7") (pinfunction "7_7") (pintype "bidirectional"))
      (node (ref "U$2") (pin "8") (pinfunction "8_8") (pintype "bidirectional"))
    )
    (net (code "145") (name "O1") (class "Default")
      (node (ref "JP7") (pin "2") (pinfunction "2_2") (pintype "passive"))
      (node (ref "JP8") (pin "2") (pinfunction "2_2") (pintype "passive"))
      (node (ref "Q1") (pin "2") (pinfunction "D_2") (pintype "passive"))
    )
    (net (code "146") (name "O2") (class "Default")
      (node (ref "JP7") (pin "3") (pinfunction "3_3") (pintype "passive"))
      (node (ref "JP8") (pin "3") (pinfunction "3_3") (pintype "passive"))
      (node (ref "Q2") (pin "2") (pinfunction "D_2") (pintype "passive"))
    )
    (net (code "147") (name "O3") (class "Default")
      (node (ref "JP7") (pin "4") (pinfunction "4_4") (pintype "passive"))
      (node (ref "JP8") (pin "4") (pinfunction "4_4") (pintype "passive"))
      (node (ref "Q4") (pin "2") (pinfunction "D_2") (pintype "passive"))
    )
    (net (code "148") (name "OUTA1") (class "Default")
      (node (ref "H1") (pin "16") (pinfunction "OUTA_16") (pintype "bidirectional"))
      (node (ref "JP6") (pin "2") (pinfunction "2_2") (pintype "passive"))
    )
    (net (code "149") (name "OUTA2") (class "Default")
      (node (ref "H2") (pin "16") (pinfunction "OUTA_16") (pintype "bidirectional"))
      (node (ref "JP5") (pin "2") (pinfunction "2_2") (pintype "passive"))
    )
    (net (code "150") (name "OUTA3") (class "Default")
      (node (ref "H3") (pin "16") (pinfunction "OUTA_16") (pintype "bidirectional"))
      (node (ref "JP4") (pin "2") (pinfunction "2_2") (pintype "passive"))
    )
    (net (code "151") (name "OUTA4") (class "Default")
      (node (ref "H4") (pin "16") (pinfunction "OUTA_16") (pintype "bidirectional"))
      (node (ref "JP3") (pin "2") (pinfunction "2_2") (pintype "passive"))
    )
    (net (code "152") (name "OUTA5") (class "Default")
      (node (ref "H5") (pin "16") (pinfunction "OUTA_16") (pintype "bidirectional"))
      (node (ref "JP2") (pin "2") (pinfunction "2_2") (pintype "passive"))
    )
    (net (code "153") (name "OUTB1") (class "Default")
      (node (ref "H1") (pin "21") (pinfunction "OUTB_21") (pintype "bidirectional"))
      (node (ref "JP6") (pin "1") (pinfunction "1_1") (pintype "passive"))
    )
    (net (code "154") (name "OUTB2") (class "Default")
      (node (ref "H2") (pin "21") (pinfunction "OUTB_21") (pintype "bidirectional"))
      (node (ref "JP5") (pin "1") (pinfunction "1_1") (pintype "passive"))
    )
    (net (code "155") (name "OUTB3") (class "Default")
      (node (ref "H3") (pin "21") (pinfunction "OUTB_21") (pintype "bidirectional"))
      (node (ref "JP4") (pin "1") (pinfunction "1_1") (pintype "passive"))
    )
    (net (code "156") (name "OUTB4") (class "Default")
      (node (ref "H4") (pin "21") (pinfunction "OUTB_21") (pintype "bidirectional"))
      (node (ref "JP3") (pin "1") (pinfunction "1_1") (pintype "passive"))
    )
    (net (code "157") (name "OUTB5") (class "Default")
      (node (ref "H5") (pin "21") (pinfunction "OUTB_21") (pintype "bidirectional"))
      (node (ref "JP2") (pin "1") (pinfunction "1_1") (pintype "passive"))
    )
    (net (code "158") (name "PFD1_1") (class "Default")
      (node (ref "H1") (pin "13") (pinfunction "PFD1_13") (pintype "bidirectional"))
      (node (ref "P1") (pin "14") (pinfunction "PB0_14") (pintype "bidirectional"))
    )
    (net (code "159") (name "PFD1_2") (class "Default")
      (node (ref "H2") (pin "13") (pinfunction "PFD1_13") (pintype "bidirectional"))
      (node (ref "P2") (pin "14") (pinfunction "PB0_14") (pintype "bidirectional"))
    )
    (net (code "160") (name "PFD1_3") (class "Default")
      (node (ref "H3") (pin "13") (pinfunction "PFD1_13") (pintype "bidirectional"))
      (node (ref "P3") (pin "14") (pinfunction "PB0_14") (pintype "bidirectional"))
    )
    (net (code "161") (name "PFD1_4") (class "Default")
      (node (ref "H4") (pin "13") (pinfunction "PFD1_13") (pintype "bidirectional"))
      (node (ref "P4") (pin "14") (pinfunction "PB0_14") (pintype "bidirectional"))
    )
    (net (code "162") (name "PFD1_5") (class "Default")
      (node (ref "H5") (pin "13") (pinfunction "PFD1_13") (pintype "bidirectional"))
      (node (ref "P5") (pin "14") (pinfunction "PB0_14") (pintype "bidirectional"))
    )
    (net (code "163") (name "PFD2_1") (class "Default")
      (node (ref "H1") (pin "11") (pinfunction "PFD2_11") (pintype "bidirectional"))
      (node (ref "P1") (pin "18") (pinfunction "PB4_18") (pintype "bidirectional"))
    )
    (net (code "164") (name "PFD2_2") (class "Default")
      (node (ref "H2") (pin "11") (pinfunction "PFD2_11") (pintype "bidirectional"))
      (node (ref "P2") (pin "18") (pinfunction "PB4_18") (pintype "bidirectional"))
    )
    (net (code "165") (name "PFD2_3") (class "Default")
      (node (ref "H3") (pin "11") (pinfunction "PFD2_11") (pintype "bidirectional"))
      (node (ref "P3") (pin "18") (pinfunction "PB4_18") (pintype "bidirectional"))
    )
    (net (code "166") (name "PFD2_4") (class "Default")
      (node (ref "H4") (pin "11") (pinfunction "PFD2_11") (pintype "bidirectional"))
      (node (ref "P4") (pin "18") (pinfunction "PB4_18") (pintype "bidirectional"))
    )
    (net (code "167") (name "PFD2_5") (class "Default")
      (node (ref "H5") (pin "11") (pinfunction "PFD2_11") (pintype "bidirectional"))
      (node (ref "P5") (pin "18") (pinfunction "PB4_18") (pintype "bidirectional"))
    )
    (net (code "168") (name "PHASE1") (class "Default")
      (node (ref "H1") (pin "3") (pinfunction "PHASE_3") (pintype "bidirectional"))
      (node (ref "P1") (pin "23") (pinfunction "PC0_23") (pintype "bidirectional"))
    )
    (net (code "169") (name "PHASE2") (class "Default")
      (node (ref "H2") (pin "3") (pinfunction "PHASE_3") (pintype "bidirectional"))
      (node (ref "P2") (pin "23") (pinfunction "PC0_23") (pintype "bidirectional"))
    )
    (net (code "170") (name "PHASE3") (class "Default")
      (node (ref "H3") (pin "3") (pinfunction "PHASE_3") (pintype "bidirectional"))
      (node (ref "P3") (pin "23") (pinfunction "PC0_23") (pintype "bidirectional"))
    )
    (net (code "171") (name "PHASE4") (class "Default")
      (node (ref "H4") (pin "3") (pinfunction "PHASE_3") (pintype "bidirectional"))
      (node (ref "P4") (pin "23") (pinfunction "PC0_23") (pintype "bidirectional"))
    )
    (net (code "172") (name "PHASE5") (class "Default")
      (node (ref "H5") (pin "3") (pinfunction "PHASE_3") (pintype "bidirectional"))
      (node (ref "P5") (pin "23") (pinfunction "PC0_23") (pintype "bidirectional"))
    )
    (net (code "173") (name "PULSE1") (class "Default")
      (node (ref "P1") (pin "11") (pinfunction "PD5_11") (pintype "bidirectional"))
      (node (ref "R8_1") (pin "2") (pinfunction "2_2") (pintype "passive"))
      (node (ref "R9_1") (pin "2") (pinfunction "2_2") (pintype "passive"))
    )
    (net (code "174") (name "PULSE2") (class "Default")
      (node (ref "P2") (pin "11") (pinfunction "PD5_11") (pintype "bidirectional"))
      (node (ref "R8_2") (pin "2") (pinfunction "2_2") (pintype "passive"))
      (node (ref "R9_2") (pin "2") (pinfunction "2_2") (pintype "passive"))
    )
    (net (code "175") (name "PULSE3") (class "Default")
      (node (ref "P3") (pin "11") (pinfunction "PD5_11") (pintype "bidirectional"))
      (node (ref "R8_3") (pin "2") (pinfunction "2_2") (pintype "passive"))
      (node (ref "R9_3") (pin "2") (pinfunction "2_2") (pintype "passive"))
    )
    (net (code "176") (name "PULSE4") (class "Default")
      (node (ref "P4") (pin "11") (pinfunction "PD5_11") (pintype "bidirectional"))
      (node (ref "R8_4") (pin "2") (pinfunction "2_2") (pintype "passive"))
      (node (ref "R9_4") (pin "2") (pinfunction "2_2") (pintype "passive"))
    )
    (net (code "177") (name "PULSE5") (class "Default")
      (node (ref "P5") (pin "11") (pinfunction "PD5_11") (pintype "bidirectional"))
      (node (ref "R8_5") (pin "2") (pinfunction "2_2") (pintype "passive"))
      (node (ref "R9_5") (pin "2") (pinfunction "2_2") (pintype "passive"))
    )
    (net (code "178") (name "PWM1") (class "Default")
      (node (ref "JP15") (pin "3") (pinfunction "3_3") (pintype "passive"))
      (node (ref "MP") (pin "11") (pinfunction "PD5_11") (pintype "bidirectional"))
    )
    (net (code "179") (name "PWM2") (class "Default")
      (node (ref "JP14") (pin "3") (pinfunction "3_3") (pintype "passive"))
      (node (ref "MP") (pin "12") (pinfunction "PD6_12") (pintype "bidirectional"))
    )
    (net (code "180") (name "R1") (class "Default")
      (node (ref "P1") (pin "2") (pinfunction "PD0_2") (pintype "bidirectional"))
    )
    (net (code "181") (name "R2") (class "Default")
      (node (ref "P2") (pin "2") (pinfunction "PD0_2") (pintype "bidirectional"))
    )
    (net (code "182") (name "R3") (class "Default")
      (node (ref "P3") (pin "2") (pinfunction "PD0_2") (pintype "bidirectional"))
    )
    (net (code "183") (name "R4") (class "Default")
      (node (ref "P4") (pin "2") (pinfunction "PD0_2") (pintype "bidirectional"))
    )
    (net (code "184") (name "R5") (class "Default")
      (node (ref "P5") (pin "2") (pinfunction "PD0_2") (pintype "bidirectional"))
    )
    (net (code "185") (name "R7") (class "Default")
      (node (ref "P6") (pin "2") (pinfunction "PD0_2") (pintype "bidirectional"))
    )
    (net (code "186") (name "REF1_1") (class "Default")
      (node (ref "P1") (pin "15") (pinfunction "PB1_15") (pintype "bidirectional"))
      (node (ref "R5_1") (pin "2") (pinfunction "2_2") (pintype "passive"))
    )
    (net (code "187") (name "REF1_2") (class "Default")
      (node (ref "P2") (pin "15") (pinfunction "PB1_15") (pintype "bidirectional"))
      (node (ref "R5_2") (pin "2") (pinfunction "2_2") (pintype "passive"))
    )
    (net (code "188") (name "REF1_3") (class "Default")
      (node (ref "P3") (pin "15") (pinfunction "PB1_15") (pintype "bidirectional"))
      (node (ref "R5_3") (pin "2") (pinfunction "2_2") (pintype "passive"))
    )
    (net (code "189") (name "REF1_4") (class "Default")
      (node (ref "P4") (pin "15") (pinfunction "PB1_15") (pintype "bidirectional"))
      (node (ref "R5_4") (pin "2") (pinfunction "2_2") (pintype "passive"))
    )
    (net (code "190") (name "REF1_5") (class "Default")
      (node (ref "P5") (pin "15") (pinfunction "PB1_15") (pintype "bidirectional"))
      (node (ref "R5_5") (pin "2") (pinfunction "2_2") (pintype "passive"))
    )
    (net (code "191") (name "RM") (class "Default")
      (node (ref "MD") (pin "3") (pinfunction "3_3") (pintype "passive"))
      (node (ref "MP") (pin "2") (pinfunction "PD0_2") (pintype "bidirectional"))
      (node (ref "Q3") (pin "2") (pinfunction "R_2") (pintype "bidirectional"))
    )
    (net (code "192") (name "S1") (class "Default")
      (node (ref "MP") (pin "15") (pinfunction "PB1_15") (pintype "bidirectional"))
      (node (ref "Q1") (pin "1") (pinfunction "G_1") (pintype "passive"))
      (node (ref "R3") (pin "P$2") (pinfunction "2_P$2") (pintype "passive"))
    )
    (net (code "193") (name "S2") (class "Default")
      (node (ref "MP") (pin "16") (pinfunction "PB2_16") (pintype "bidirectional"))
      (node (ref "Q2") (pin "1") (pinfunction "G_1") (pintype "passive"))
      (node (ref "R6") (pin "P$2") (pinfunction "2_P$2") (pintype "passive"))
    )
    (net (code "194") (name "S3") (class "Default")
      (node (ref "MP") (pin "17") (pinfunction "PB3_17") (pintype "bidirectional"))
      (node (ref "Q4") (pin "1") (pinfunction "G_1") (pintype "passive"))
      (node (ref "R7") (pin "P$2") (pinfunction "2_P$2") (pintype "passive"))
    )
    (net (code "195") (name "S6") (class "Default")
      (node (ref "J6") (pin "P$2") (pinfunction "2_P$2") (pintype "bidirectional"))
      (node (ref "P6") (pin "1") (pinfunction "PC6_1") (pintype "bidirectional"))
      (node (ref "R1_6") (pin "1") (pinfunction "1_1") (pintype "passive"))
      (node (ref "R26") (pin "2") (pinfunction "2_2") (pintype "passive"))
    )
    (net (code "196") (name "SCL") (class "Default")
      (node (ref "MP") (pin "28") (pinfunction "PC5_28") (pintype "bidirectional"))
      (node (ref "P1") (pin "28") (pinfunction "PC5_28") (pintype "bidirectional"))
      (node (ref "P2") (pin "28") (pinfunction "PC5_28") (pintype "bidirectional"))
      (node (ref "P3") (pin "28") (pinfunction "PC5_28") (pintype "bidirectional"))
      (node (ref "P4") (pin "28") (pinfunction "PC5_28") (pintype "bidirectional"))
      (node (ref "P5") (pin "28") (pinfunction "PC5_28") (pintype "bidirectional"))
      (node (ref "P6") (pin "28") (pinfunction "PC5_28") (pintype "bidirectional"))
      (node (ref "R1") (pin "P$2") (pinfunction "2_P$2") (pintype "passive"))
    )
    (net (code "197") (name "SD6") (class "Default")
      (node (ref "P6") (pin "5") (pinfunction "PD3_5") (pintype "bidirectional"))
      (node (ref "U$26") (pin "4") (pinfunction "DI_4") (pintype "bidirectional"))
    )
    (net (code "198") (name "SDA") (class "Default")
      (node (ref "MP") (pin "27") (pinfunction "PC4_27") (pintype "bidirectional"))
      (node (ref "P1") (pin "27") (pinfunction "PC4_27") (pintype "bidirectional"))
      (node (ref "P2") (pin "27") (pinfunction "PC4_27") (pintype "bidirectional"))
      (node (ref "P3") (pin "27") (pinfunction "PC4_27") (pintype "bidirectional"))
      (node (ref "P4") (pin "27") (pinfunction "PC4_27") (pintype "bidirectional"))
      (node (ref "P5") (pin "27") (pinfunction "PC4_27") (pintype "bidirectional"))
      (node (ref "P6") (pin "27") (pinfunction "PC4_27") (pintype "bidirectional"))
      (node (ref "R2") (pin "P$2") (pinfunction "2_P$2") (pintype "passive"))
    )
    (net (code "199") (name "SLEEP1_1") (class "Default")
      (node (ref "H1") (pin "22") (pinfunction "SLEEP_22") (pintype "bidirectional"))
      (node (ref "P1") (pin "24") (pinfunction "PC1_24") (pintype "bidirectional"))
    )
    (net (code "200") (name "SLEEP1_2") (class "Default")
      (node (ref "H2") (pin "22") (pinfunction "SLEEP_22") (pintype "bidirectional"))
      (node (ref "P2") (pin "24") (pinfunction "PC1_24") (pintype "bidirectional"))
    )
    (net (code "201") (name "SLEEP1_3") (class "Default")
      (node (ref "H3") (pin "22") (pinfunction "SLEEP_22") (pintype "bidirectional"))
      (node (ref "P3") (pin "24") (pinfunction "PC1_24") (pintype "bidirectional"))
    )
    (net (code "202") (name "SLEEP1_4") (class "Default")
      (node (ref "H4") (pin "22") (pinfunction "SLEEP_22") (pintype "bidirectional"))
      (node (ref "P4") (pin "24") (pinfunction "PC1_24") (pintype "bidirectional"))
    )
    (net (code "203") (name "SLEEP1_5") (class "Default")
      (node (ref "H5") (pin "22") (pinfunction "SLEEP_22") (pintype "bidirectional"))
      (node (ref "P5") (pin "24") (pinfunction "PC1_24") (pintype "bidirectional"))
    )
    (net (code "204") (name "SR6") (class "Default")
      (node (ref "P6") (pin "4") (pinfunction "PD2_4") (pintype "bidirectional"))
      (node (ref "U$26") (pin "1") (pinfunction "RO_1") (pintype "bidirectional"))
    )
    (net (code "205") (name "V5") (class "Default")
      (node (ref "C10") (pin "1") (pinfunction "1_1") (pintype "passive"))
      (node (ref "C1_1") (pin "2") (pinfunction "2_2") (pintype "passive"))
      (node (ref "C1_2") (pin "2") (pinfunction "2_2") (pintype "passive"))
      (node (ref "C1_3") (pin "2") (pinfunction "2_2") (pintype "passive"))
      (node (ref "C1_4") (pin "2") (pinfunction "2_2") (pintype "passive"))
      (node (ref "C1_5") (pin "2") (pinfunction "2_2") (pintype "passive"))
      (node (ref "C1_6") (pin "2") (pinfunction "2_2") (pintype "passive"))
      (node (ref "C1_M") (pin "2") (pinfunction "2_2") (pintype "passive"))
      (node (ref "C4_1") (pin "1") (pinfunction "1_1") (pintype "passive"))
      (node (ref "C4_2") (pin "1") (pinfunction "1_1") (pintype "passive"))
      (node (ref "C4_3") (pin "1") (pinfunction "1_1") (pintype "passive"))
      (node (ref "C4_4") (pin "1") (pinfunction "1_1") (pintype "passive"))
      (node (ref "C4_5") (pin "1") (pinfunction "1_1") (pintype "passive"))
      (node (ref "C4_6") (pin "1") (pinfunction "1_1") (pintype "passive"))
      (node (ref "C4_M") (pin "1") (pinfunction "1_1") (pintype "passive"))
      (node (ref "C7_1") (pin "1") (pinfunction "1_1") (pintype "passive"))
      (node (ref "C7_2") (pin "1") (pinfunction "1_1") (pintype "passive"))
      (node (ref "C7_3") (pin "1") (pinfunction "1_1") (pintype "passive"))
      (node (ref "C7_4") (pin "1") (pinfunction "1_1") (pintype "passive"))
      (node (ref "C7_5") (pin "1") (pinfunction "1_1") (pintype "passive"))
      (node (ref "CV4") (pin "1") (pinfunction "1_1") (pintype "passive"))
      (node (ref "E1") (pin "4") (pinfunction "4_4") (pintype "passive"))
      (node (ref "E2") (pin "4") (pinfunction "4_4") (pintype "passive"))
      (node (ref "E3") (pin "4") (pinfunction "4_4") (pintype "passive"))
      (node (ref "E4") (pin "4") (pinfunction "4_4") (pintype "passive"))
      (node (ref "E5") (pin "4") (pinfunction "4_4") (pintype "passive"))
      (node (ref "H1") (pin "9") (pinfunction "VDD_9") (pintype "bidirectional"))
      (node (ref "H2") (pin "9") (pinfunction "VDD_9") (pintype "bidirectional"))
      (node (ref "H3") (pin "9") (pinfunction "VDD_9") (pintype "bidirectional"))
      (node (ref "H4") (pin "9") (pinfunction "VDD_9") (pintype "bidirectional"))
      (node (ref "H5") (pin "9") (pinfunction "VDD_9") (pintype "bidirectional"))
      (node (ref "JP10") (pin "1") (pinfunction "1_1") (pintype "passive"))
      (node (ref "JP11") (pin "1") (pinfunction "1_1") (pintype "passive"))
      (node (ref "JP12") (pin "1") (pinfunction "1_1") (pintype "passive"))
      (node (ref "JP13") (pin "1") (pinfunction "1_1") (pintype "passive"))
      (node (ref "JP14") (pin "2") (pinfunction "2_2") (pintype "passive"))
      (node (ref "JP15") (pin "2") (pinfunction "2_2") (pintype "passive"))
      (node (ref "JP9") (pin "1") (pinfunction "1_1") (pintype "passive"))
      (node (ref "MP") (pin "20") (pinfunction "AVCC_20") (pintype "bidirectional"))
      (node (ref "MP") (pin "7") (pinfunction "VCC_7") (pintype "bidirectional"))
      (node (ref "P1") (pin "20") (pinfunction "AVCC_20") (pintype "bidirectional"))
      (node (ref "P1") (pin "7") (pinfunction "VCC_7") (pintype "bidirectional"))
      (node (ref "P2") (pin "20") (pinfunction "AVCC_20") (pintype "bidirectional"))
      (node (ref "P2") (pin "7") (pinfunction "VCC_7") (pintype "bidirectional"))
      (node (ref "P3") (pin "20") (pinfunction "AVCC_20") (pintype "bidirectional"))
      (node (ref "P3") (pin "7") (pinfunction "VCC_7") (pintype "bidirectional"))
      (node (ref "P4") (pin "20") (pinfunction "AVCC_20") (pintype "bidirectional"))
      (node (ref "P4") (pin "7") (pinfunction "VCC_7") (pintype "bidirectional"))
      (node (ref "P5") (pin "20") (pinfunction "AVCC_20") (pintype "bidirectional"))
      (node (ref "P5") (pin "7") (pinfunction "VCC_7") (pintype "bidirectional"))
      (node (ref "P6") (pin "20") (pinfunction "AVCC_20") (pintype "bidirectional"))
      (node (ref "P6") (pin "7") (pinfunction "VCC_7") (pintype "bidirectional"))
      (node (ref "Q3") (pin "1") (pinfunction "VCC_1") (pintype "bidirectional"))
      (node (ref "Q5") (pin "3") (pinfunction "VOUT_3") (pintype "bidirectional"))
      (node (ref "R1") (pin "P$1") (pinfunction "1_P$1") (pintype "passive"))
      (node (ref "R1_1") (pin "2") (pinfunction "2_2") (pintype "passive"))
      (node (ref "R1_2") (pin "2") (pinfunction "2_2") (pintype "passive"))
      (node (ref "R1_3") (pin "2") (pinfunction "2_2") (pintype "passive"))
      (node (ref "R1_4") (pin "2") (pinfunction "2_2") (pintype "passive"))
      (node (ref "R1_5") (pin "2") (pinfunction "2_2") (pintype "passive"))
      (node (ref "R1_6") (pin "2") (pinfunction "2_2") (pintype "passive"))
      (node (ref "R1_M") (pin "2") (pinfunction "2_2") (pintype "passive"))
      (node (ref "R2") (pin "P$1") (pinfunction "1_P$1") (pintype "passive"))
      (node (ref "R4_1") (pin "1") (pinfunction "1_1") (pintype "passive"))
      (node (ref "R4_2") (pin "1") (pinfunction "1_1") (pintype "passive"))
      (node (ref "R4_3") (pin "1") (pinfunction "1_1") (pintype "passive"))
      (node (ref "R4_4") (pin "1") (pinfunction "1_1") (pintype "passive"))
      (node (ref "R4_5") (pin "1") (pinfunction "1_1") (pintype "passive"))
      (node (ref "U$26") (pin "8") (pinfunction "VCC_8") (pintype "bidirectional"))
    )
    (net (code "206") (name "VIN") (class "Default")
      (node (ref "C10_1") (pin "2") (pinfunction "2_2") (pintype "passive"))
      (node (ref "C10_2") (pin "2") (pinfunction "2_2") (pintype "passive"))
      (node (ref "C10_3") (pin "2") (pinfunction "2_2") (pintype "passive"))
      (node (ref "C10_4") (pin "2") (pinfunction "2_2") (pintype "passive"))
      (node (ref "C10_5") (pin "2") (pinfunction "2_2") (pintype "passive"))
      (node (ref "CV3") (pin "1") (pinfunction "1_1") (pintype "passive"))
      (node (ref "H1") (pin "20") (pinfunction "VBB_20") (pintype "bidirectional"))
      (node (ref "H2") (pin "20") (pinfunction "VBB_20") (pintype "bidirectional"))
      (node (ref "H3") (pin "20") (pinfunction "VBB_20") (pintype "bidirectional"))
      (node (ref "H4") (pin "20") (pinfunction "VBB_20") (pintype "bidirectional"))
      (node (ref "H5") (pin "20") (pinfunction "VBB_20") (pintype "bidirectional"))
      (node (ref "JP1") (pin "1") (pinfunction "1_1") (pintype "passive"))
      (node (ref "JP7") (pin "1") (pinfunction "1_1") (pintype "passive"))
      (node (ref "JP8") (pin "1") (pinfunction "1_1") (pintype "passive"))
      (node (ref "O6") (pin "2") (pinfunction "2_2") (pintype "passive"))
      (node (ref "Q5") (pin "1") (pinfunction "VIN_1") (pintype "bidirectional"))
    )
    (net (code "207") (name "unconnected-(MP-PB4-Pad18)") (class "Default")
      (node (ref "MP") (pin "18") (pinfunction "PB4_18") (pintype "bidirectional"))
    )
    (net (code "208") (name "unconnected-(MP-PB5-Pad19)") (class "Default")
      (node (ref "MP") (pin "19") (pinfunction "PB5_19") (pintype "bidirectional"))
    )
    (net (code "209") (name "unconnected-(MP-PC0-Pad23)") (class "Default")
      (node (ref "MP") (pin "23") (pinfunction "PC0_23") (pintype "bidirectional"))
    )
    (net (code "210") (name "unconnected-(MP-PC1-Pad24)") (class "Default")
      (node (ref "MP") (pin "24") (pinfunction "PC1_24") (pintype "bidirectional"))
    )
    (net (code "211") (name "unconnected-(MP-PC2-Pad25)") (class "Default")
      (node (ref "MP") (pin "25") (pinfunction "PC2_25") (pintype "bidirectional"))
    )
    (net (code "212") (name "unconnected-(MP-PC3-Pad26)") (class "Default")
      (node (ref "MP") (pin "26") (pinfunction "PC3_26") (pintype "bidirectional"))
    )
    (net (code "213") (name "unconnected-(P1-PC2-Pad25)") (class "Default")
      (node (ref "P1") (pin "25") (pinfunction "PC2_25") (pintype "bidirectional"))
    )
    (net (code "214") (name "unconnected-(P1-PD4-Pad6)") (class "Default")
      (node (ref "P1") (pin "6") (pinfunction "PD4_6") (pintype "bidirectional"))
    )
    (net (code "215") (name "unconnected-(P2-PC2-Pad25)") (class "Default")
      (node (ref "P2") (pin "25") (pinfunction "PC2_25") (pintype "bidirectional"))
    )
    (net (code "216") (name "unconnected-(P2-PD4-Pad6)") (class "Default")
      (node (ref "P2") (pin "6") (pinfunction "PD4_6") (pintype "bidirectional"))
    )
    (net (code "217") (name "unconnected-(P3-PC2-Pad25)") (class "Default")
      (node (ref "P3") (pin "25") (pinfunction "PC2_25") (pintype "bidirectional"))
    )
    (net (code "218") (name "unconnected-(P3-PD4-Pad6)") (class "Default")
      (node (ref "P3") (pin "6") (pinfunction "PD4_6") (pintype "bidirectional"))
    )
    (net (code "219") (name "unconnected-(P4-PC2-Pad25)") (class "Default")
      (node (ref "P4") (pin "25") (pinfunction "PC2_25") (pintype "bidirectional"))
    )
    (net (code "220") (name "unconnected-(P4-PD4-Pad6)") (class "Default")
      (node (ref "P4") (pin "6") (pinfunction "PD4_6") (pintype "bidirectional"))
    )
    (net (code "221") (name "unconnected-(P5-PC2-Pad25)") (class "Default")
      (node (ref "P5") (pin "25") (pinfunction "PC2_25") (pintype "bidirectional"))
    )
    (net (code "222") (name "unconnected-(P5-PD4-Pad6)") (class "Default")
      (node (ref "P5") (pin "6") (pinfunction "PD4_6") (pintype "bidirectional"))
    )
    (net (code "223") (name "unconnected-(P6-PB0-Pad14)") (class "Default")
      (node (ref "P6") (pin "14") (pinfunction "PB0_14") (pintype "bidirectional"))
    )
    (net (code "224") (name "unconnected-(P6-PB1-Pad15)") (class "Default")
      (node (ref "P6") (pin "15") (pinfunction "PB1_15") (pintype "bidirectional"))
    )
    (net (code "225") (name "unconnected-(P6-PB2-Pad16)") (class "Default")
      (node (ref "P6") (pin "16") (pinfunction "PB2_16") (pintype "bidirectional"))
    )
    (net (code "226") (name "unconnected-(P6-PB3-Pad17)") (class "Default")
      (node (ref "P6") (pin "17") (pinfunction "PB3_17") (pintype "bidirectional"))
    )
    (net (code "227") (name "unconnected-(P6-PB4-Pad18)") (class "Default")
      (node (ref "P6") (pin "18") (pinfunction "PB4_18") (pintype "bidirectional"))
    )
    (net (code "228") (name "unconnected-(P6-PB5-Pad19)") (class "Default")
      (node (ref "P6") (pin "19") (pinfunction "PB5_19") (pintype "bidirectional"))
    )
    (net (code "229") (name "unconnected-(P6-PC0-Pad23)") (class "Default")
      (node (ref "P6") (pin "23") (pinfunction "PC0_23") (pintype "bidirectional"))
    )
    (net (code "230") (name "unconnected-(P6-PC1-Pad24)") (class "Default")
      (node (ref "P6") (pin "24") (pinfunction "PC1_24") (pintype "bidirectional"))
    )
    (net (code "231") (name "unconnected-(P6-PC2-Pad25)") (class "Default")
      (node (ref "P6") (pin "25") (pinfunction "PC2_25") (pintype "bidirectional"))
    )
    (net (code "232") (name "unconnected-(P6-PC3-Pad26)") (class "Default")
      (node (ref "P6") (pin "26") (pinfunction "PC3_26") (pintype "bidirectional"))
    )
    (net (code "233") (name "unconnected-(P6-PD5-Pad11)") (class "Default")
      (node (ref "P6") (pin "11") (pinfunction "PD5_11") (pintype "bidirectional"))
    )
    (net (code "234") (name "unconnected-(U$2-Pad4)") (class "Default")
      (node (ref "U$2") (pin "4") (pinfunction "4_4") (pintype "bidirectional"))
    )
    (net (code "235") (name "unconnected-(U$2-Pad5)") (class "Default")
      (node (ref "U$2") (pin "5") (pinfunction "5_5") (pintype "bidirectional"))
    )
  )
)
